# S7G7_footprint_simplified_w_ethernet_Pow.net
KiCad netlist of a schematic drawn in EAGLE
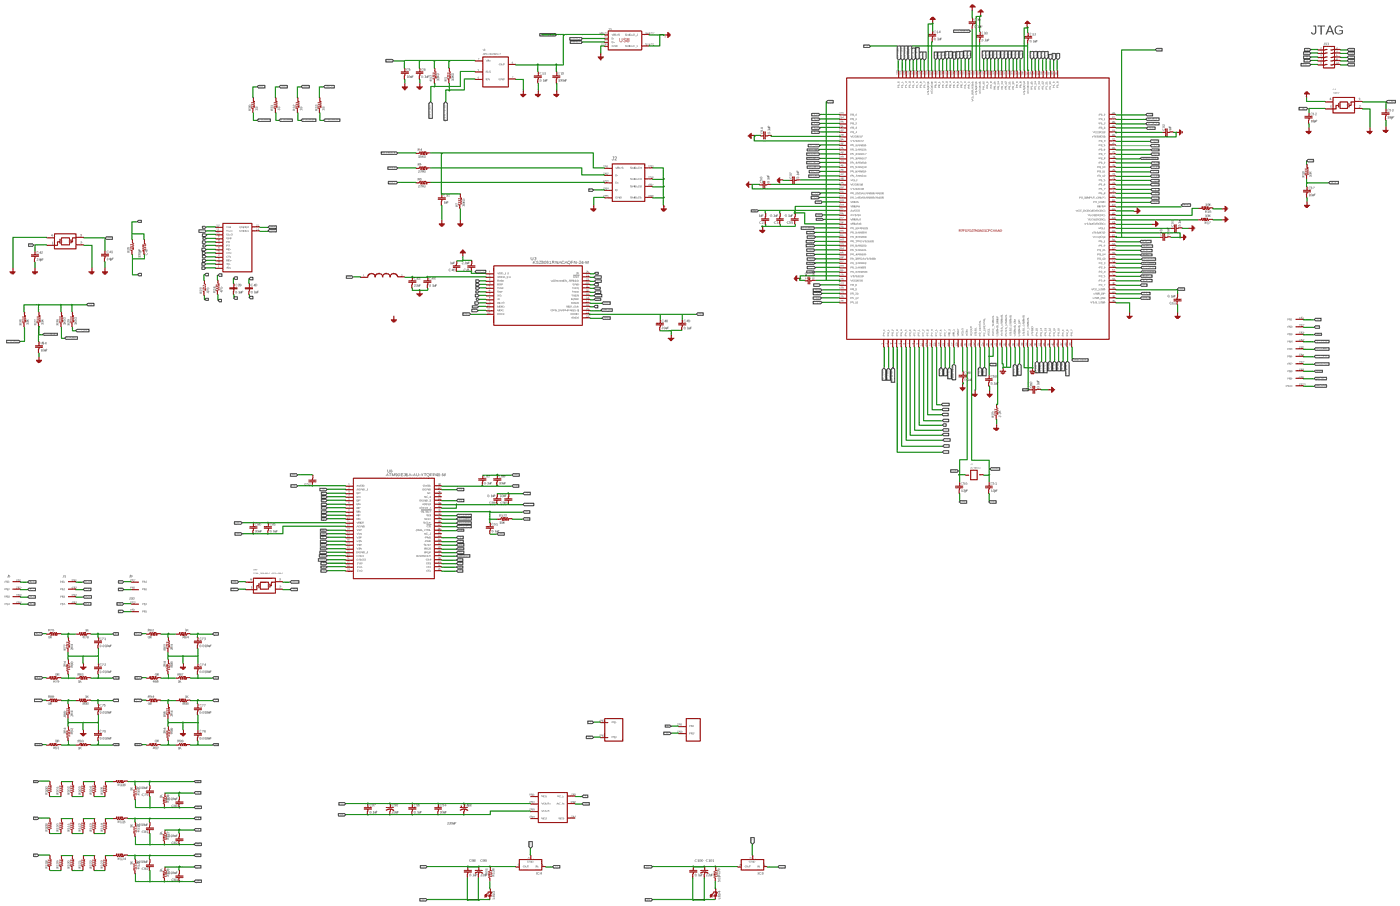
[diagram p0: schematic, sheet 1, overview]
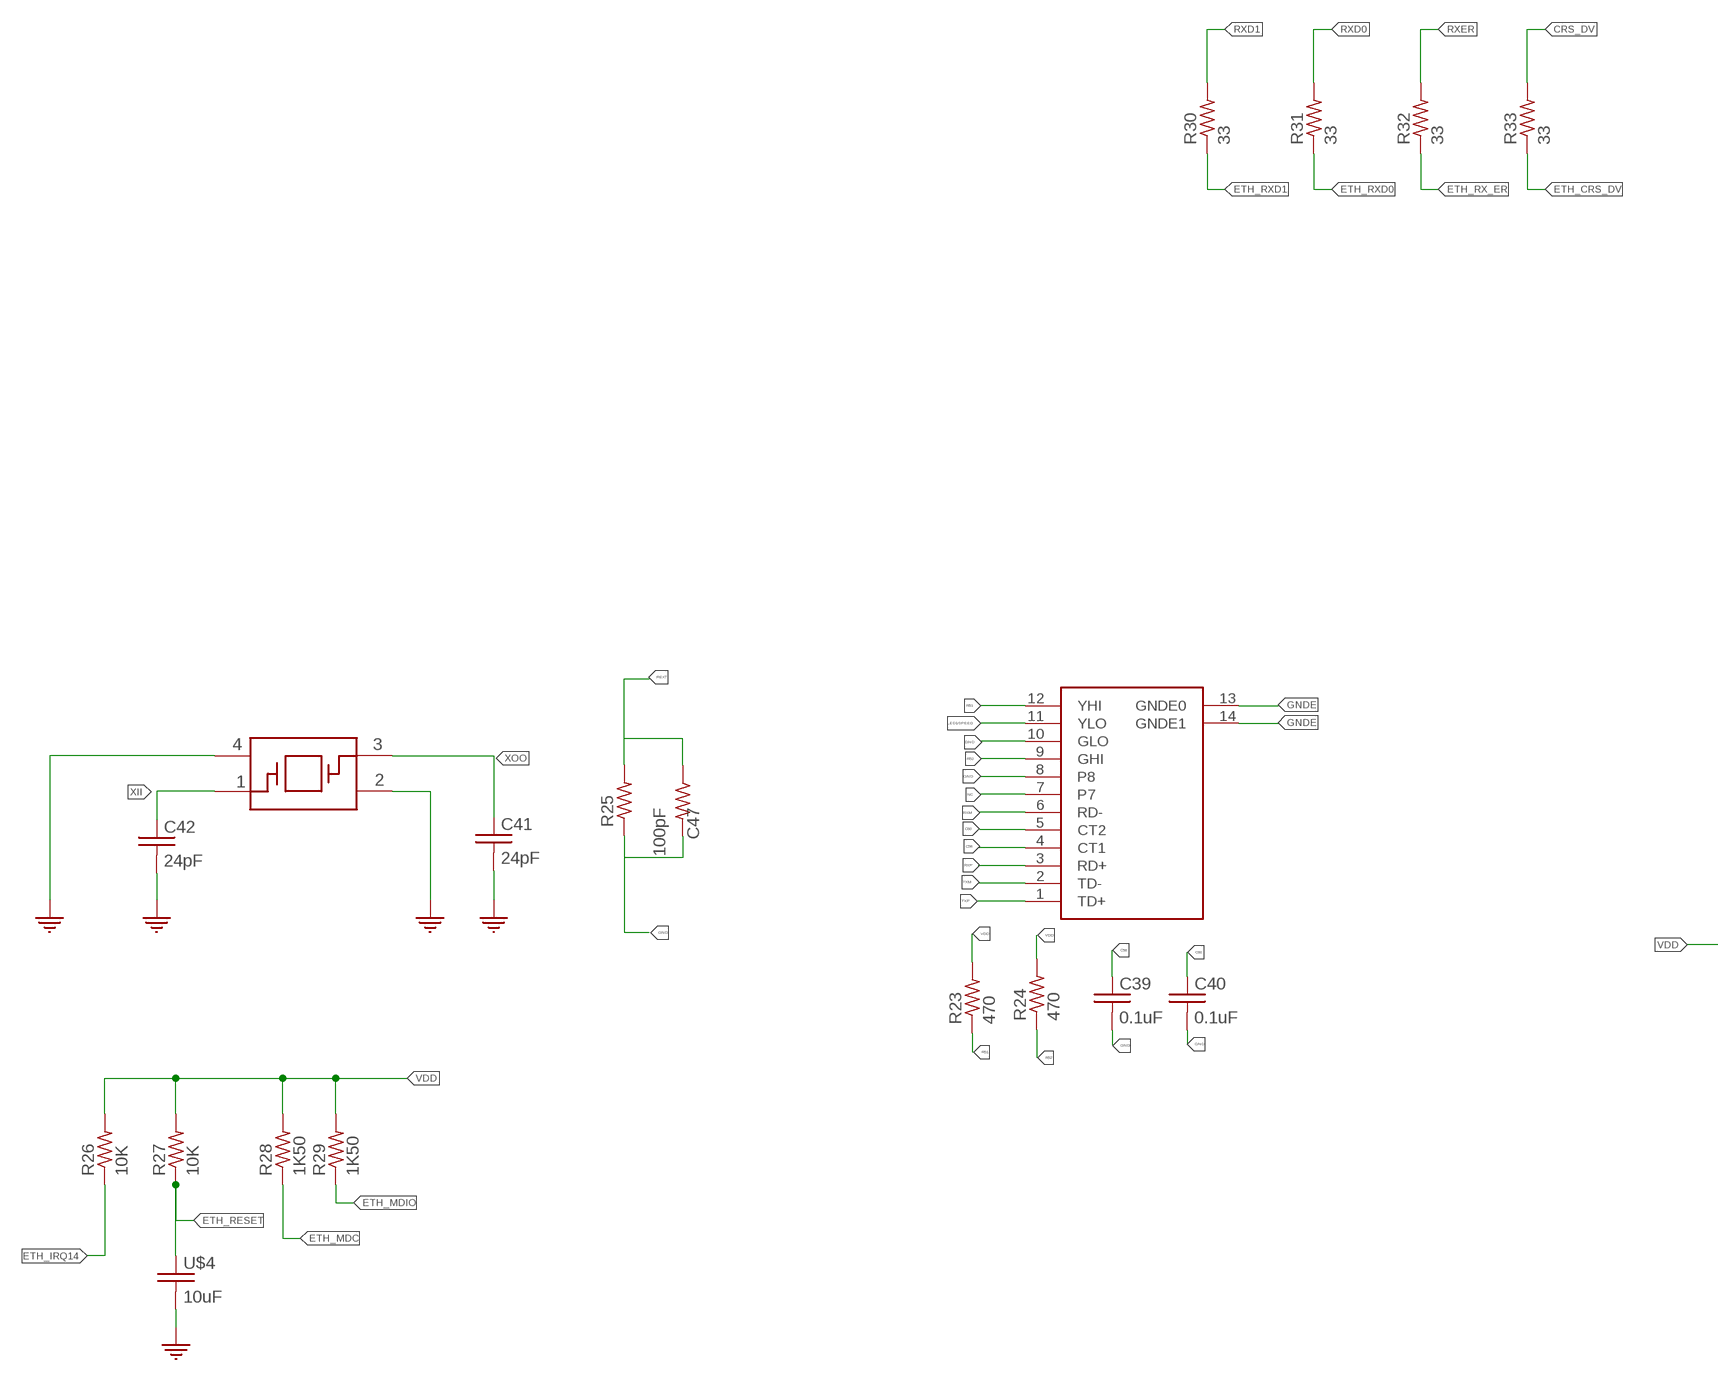
[diagram p1: schematic, sheet 1, part 1 of 6]
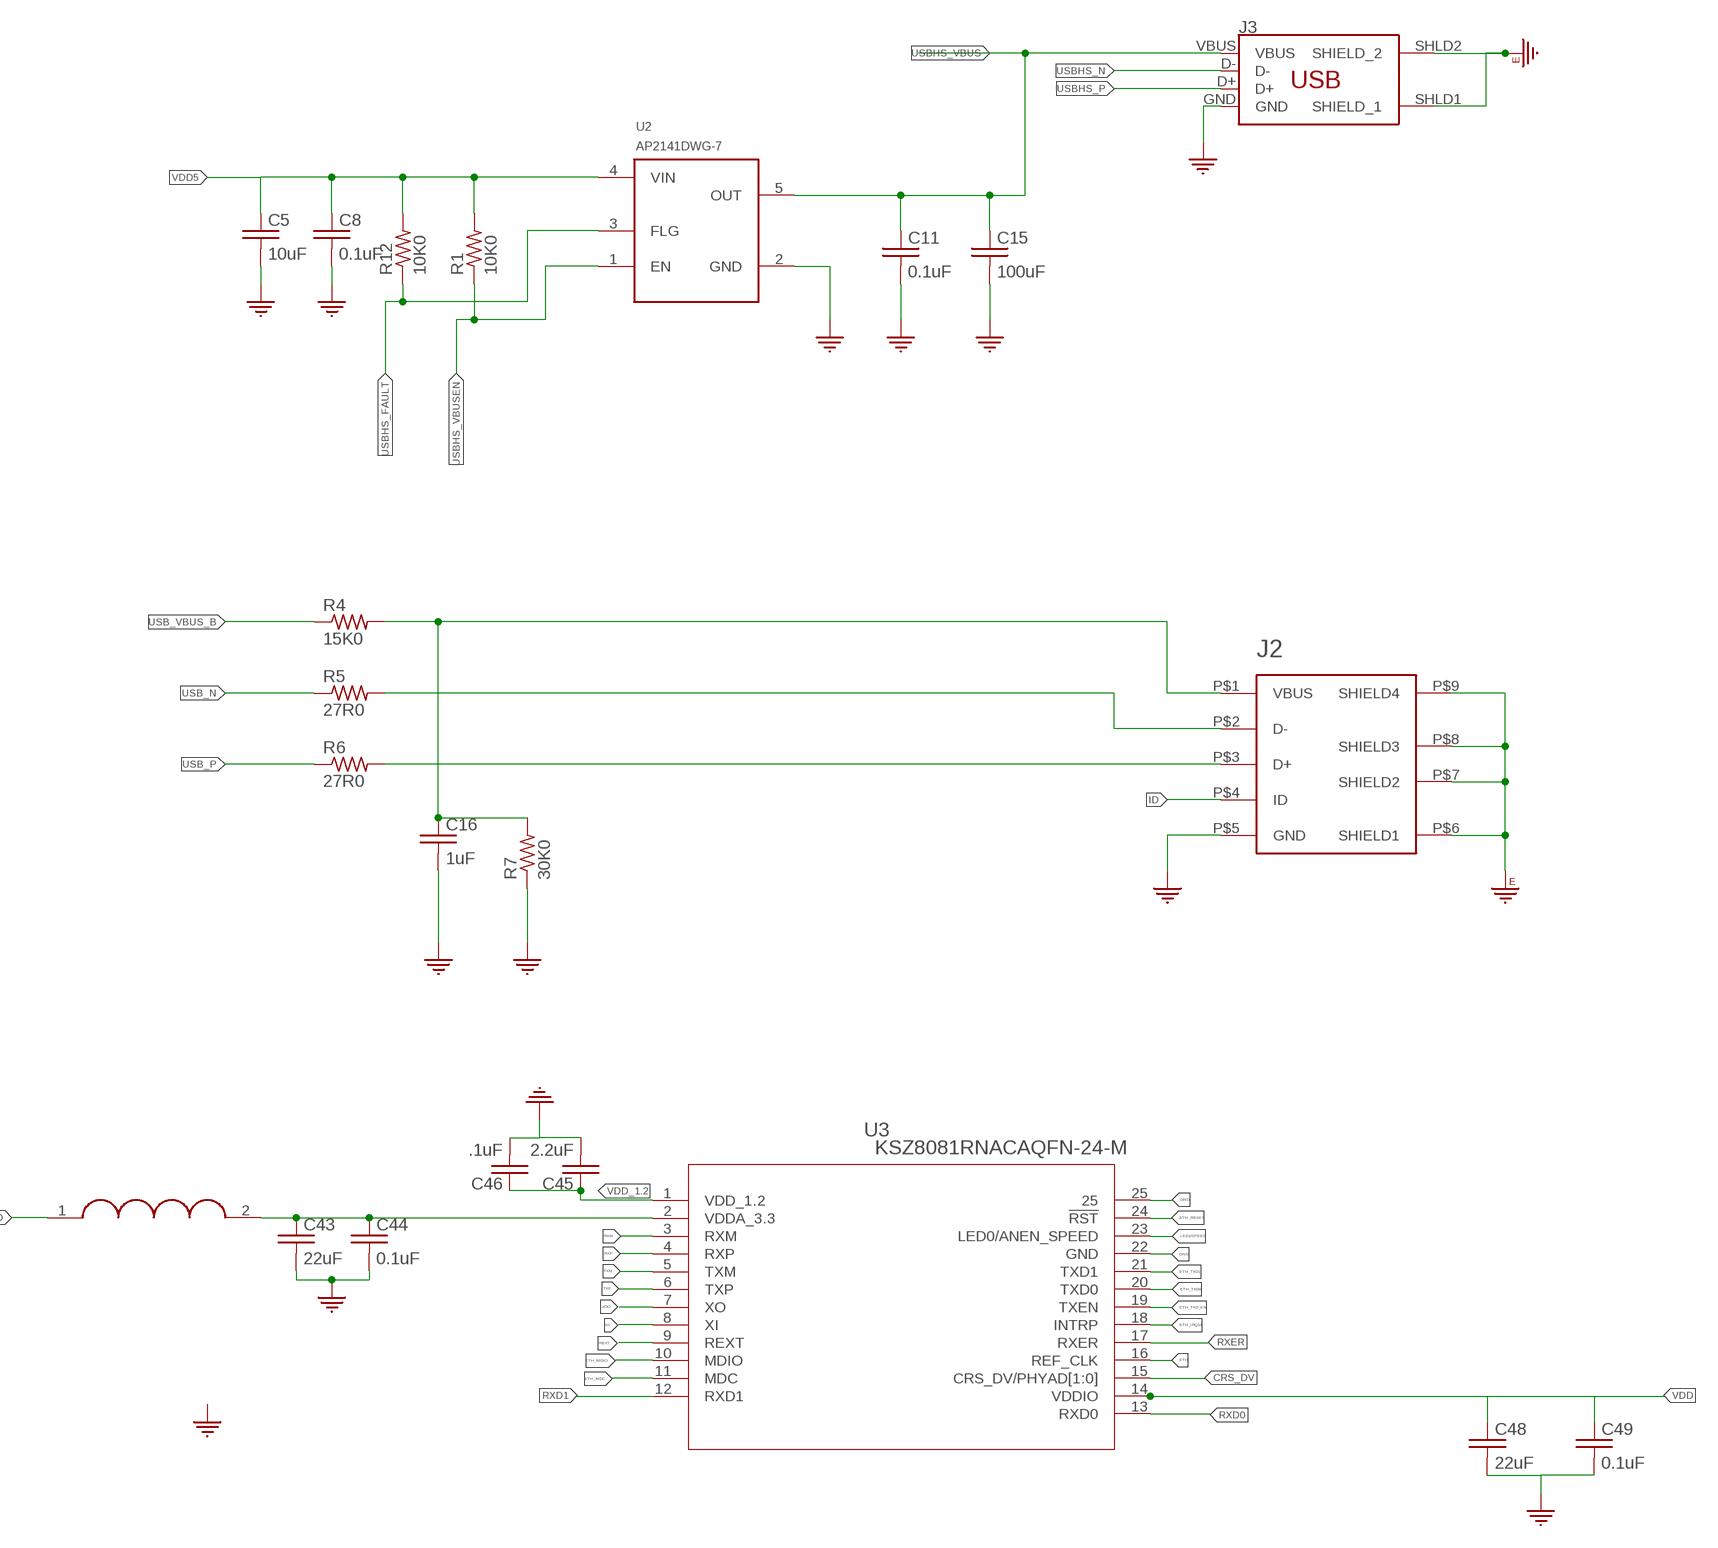
[diagram p2: schematic, sheet 1, part 2 of 6]
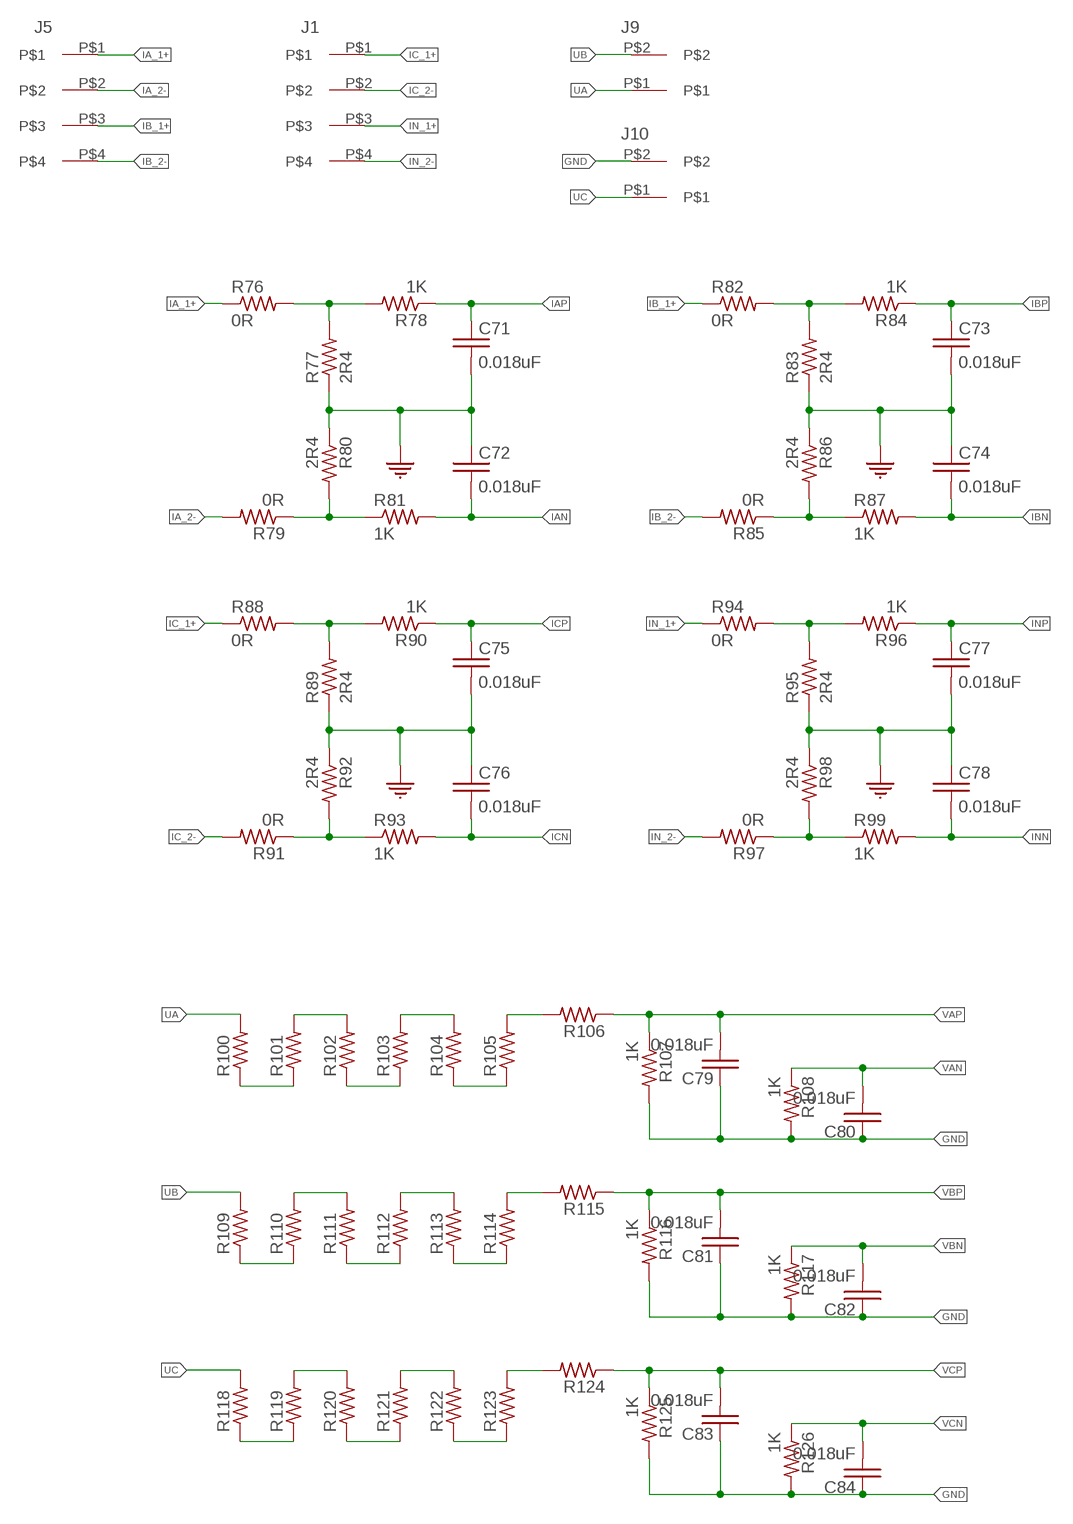
[diagram p3: schematic, sheet 1, part 3 of 6]
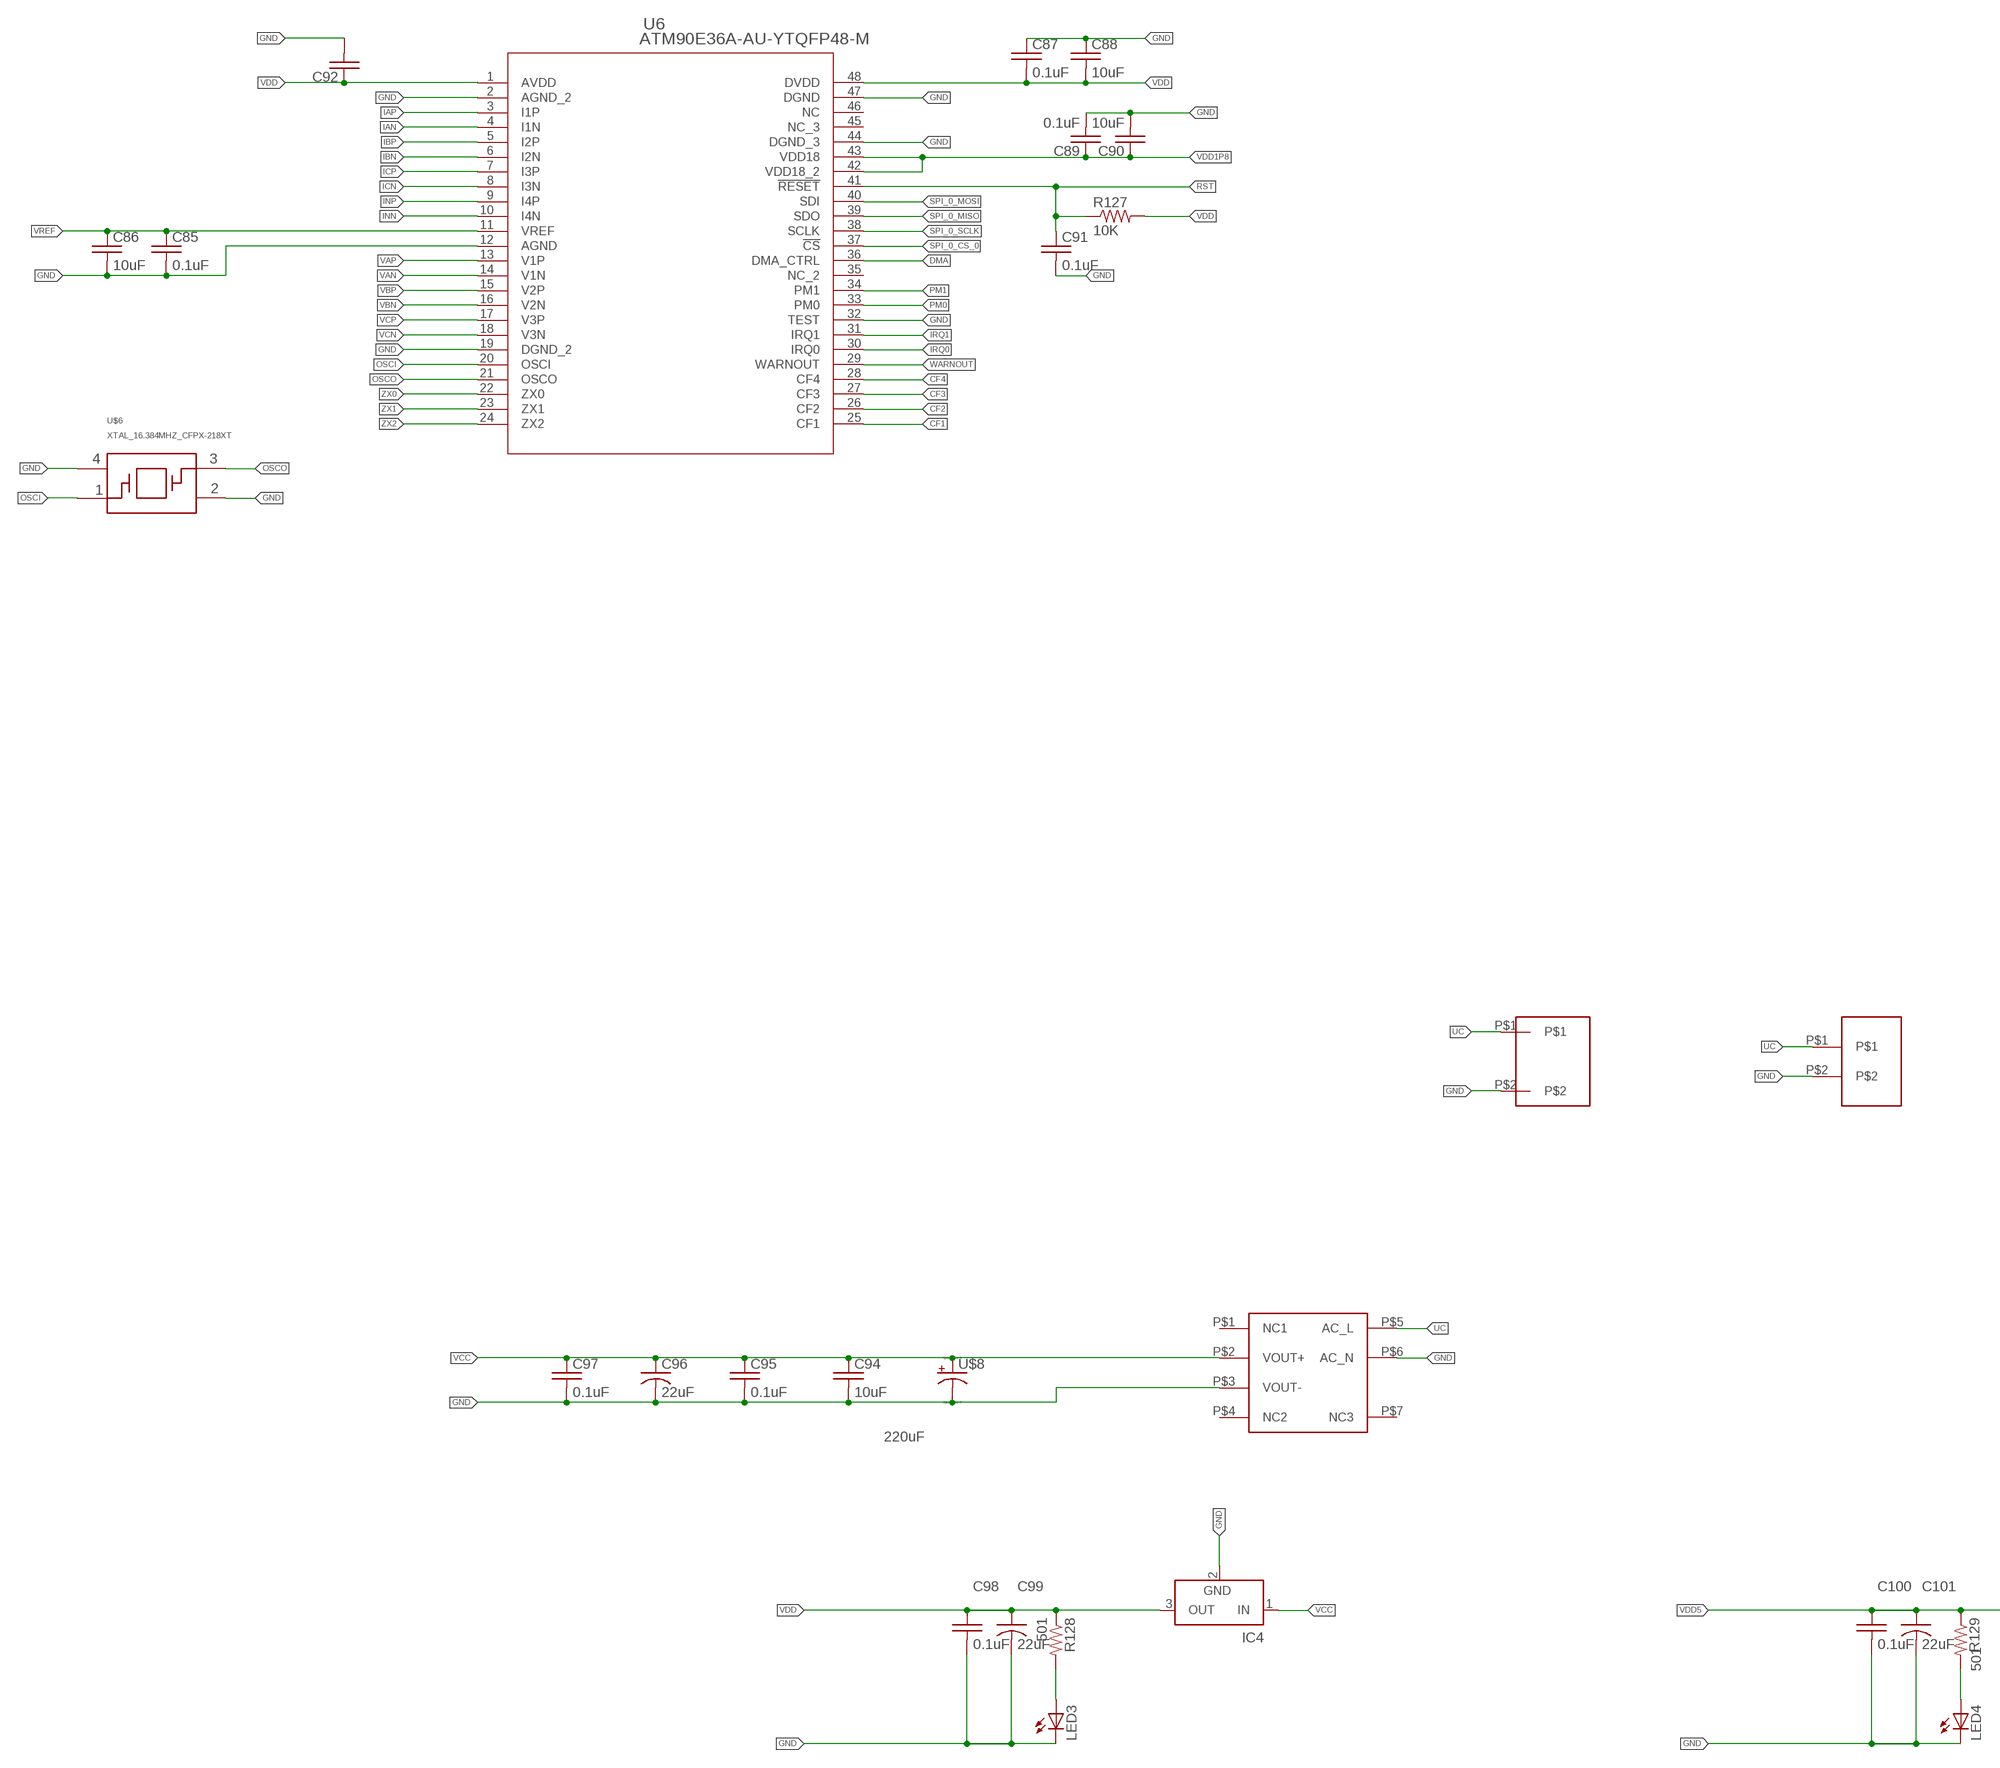
[diagram p4: schematic, sheet 1, part 4 of 6]
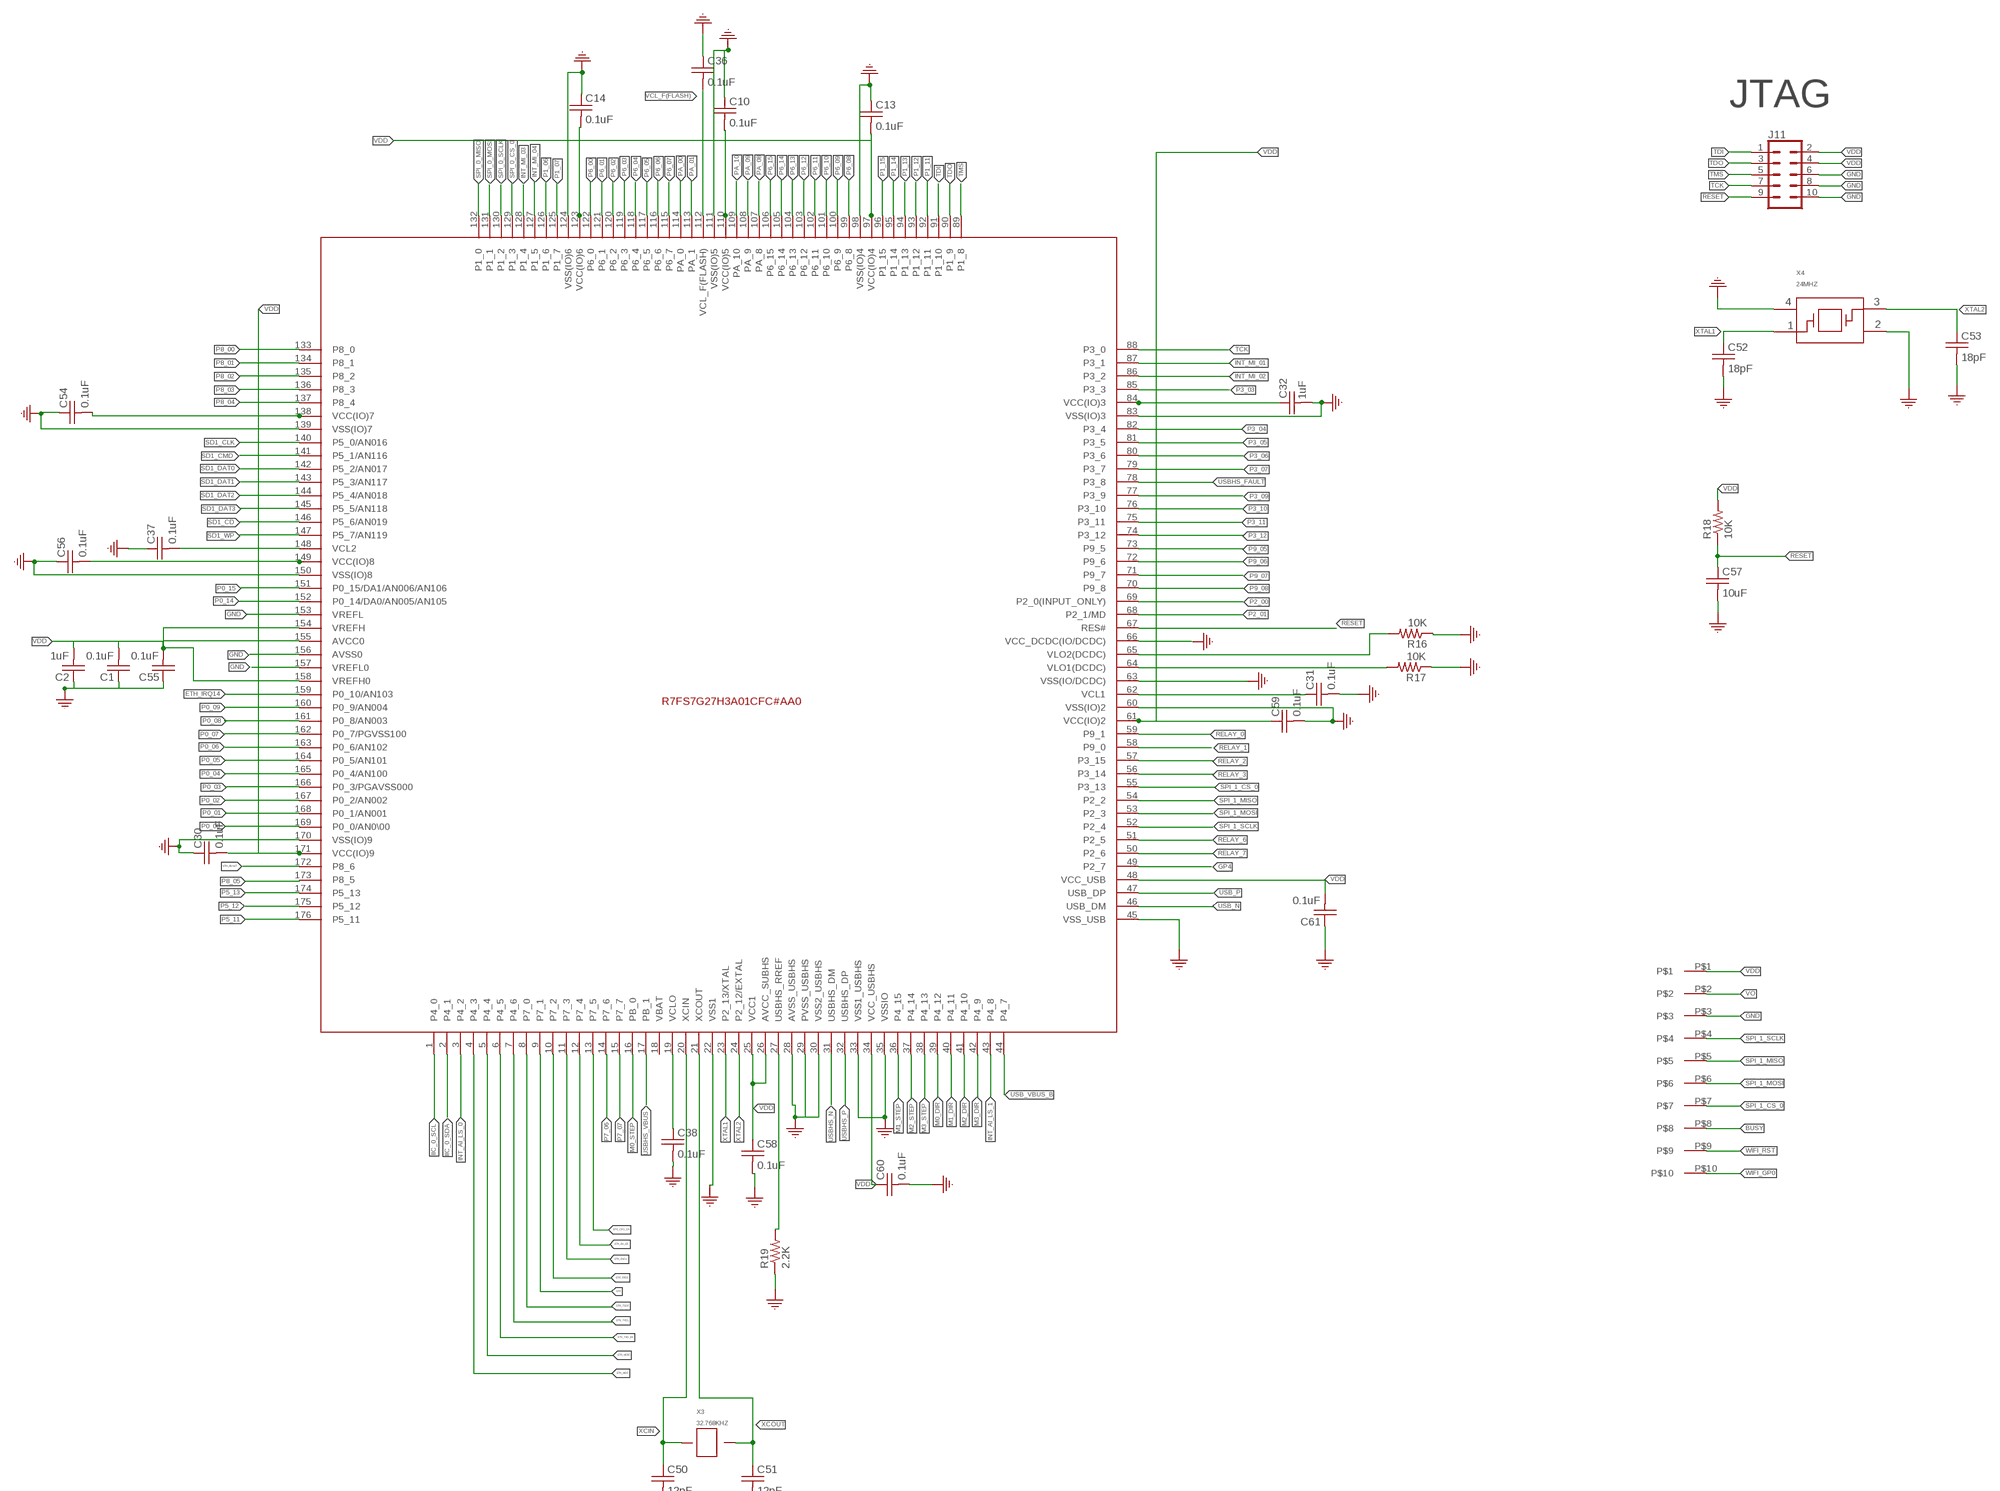
[diagram p5: schematic, sheet 1, part 5 of 6]
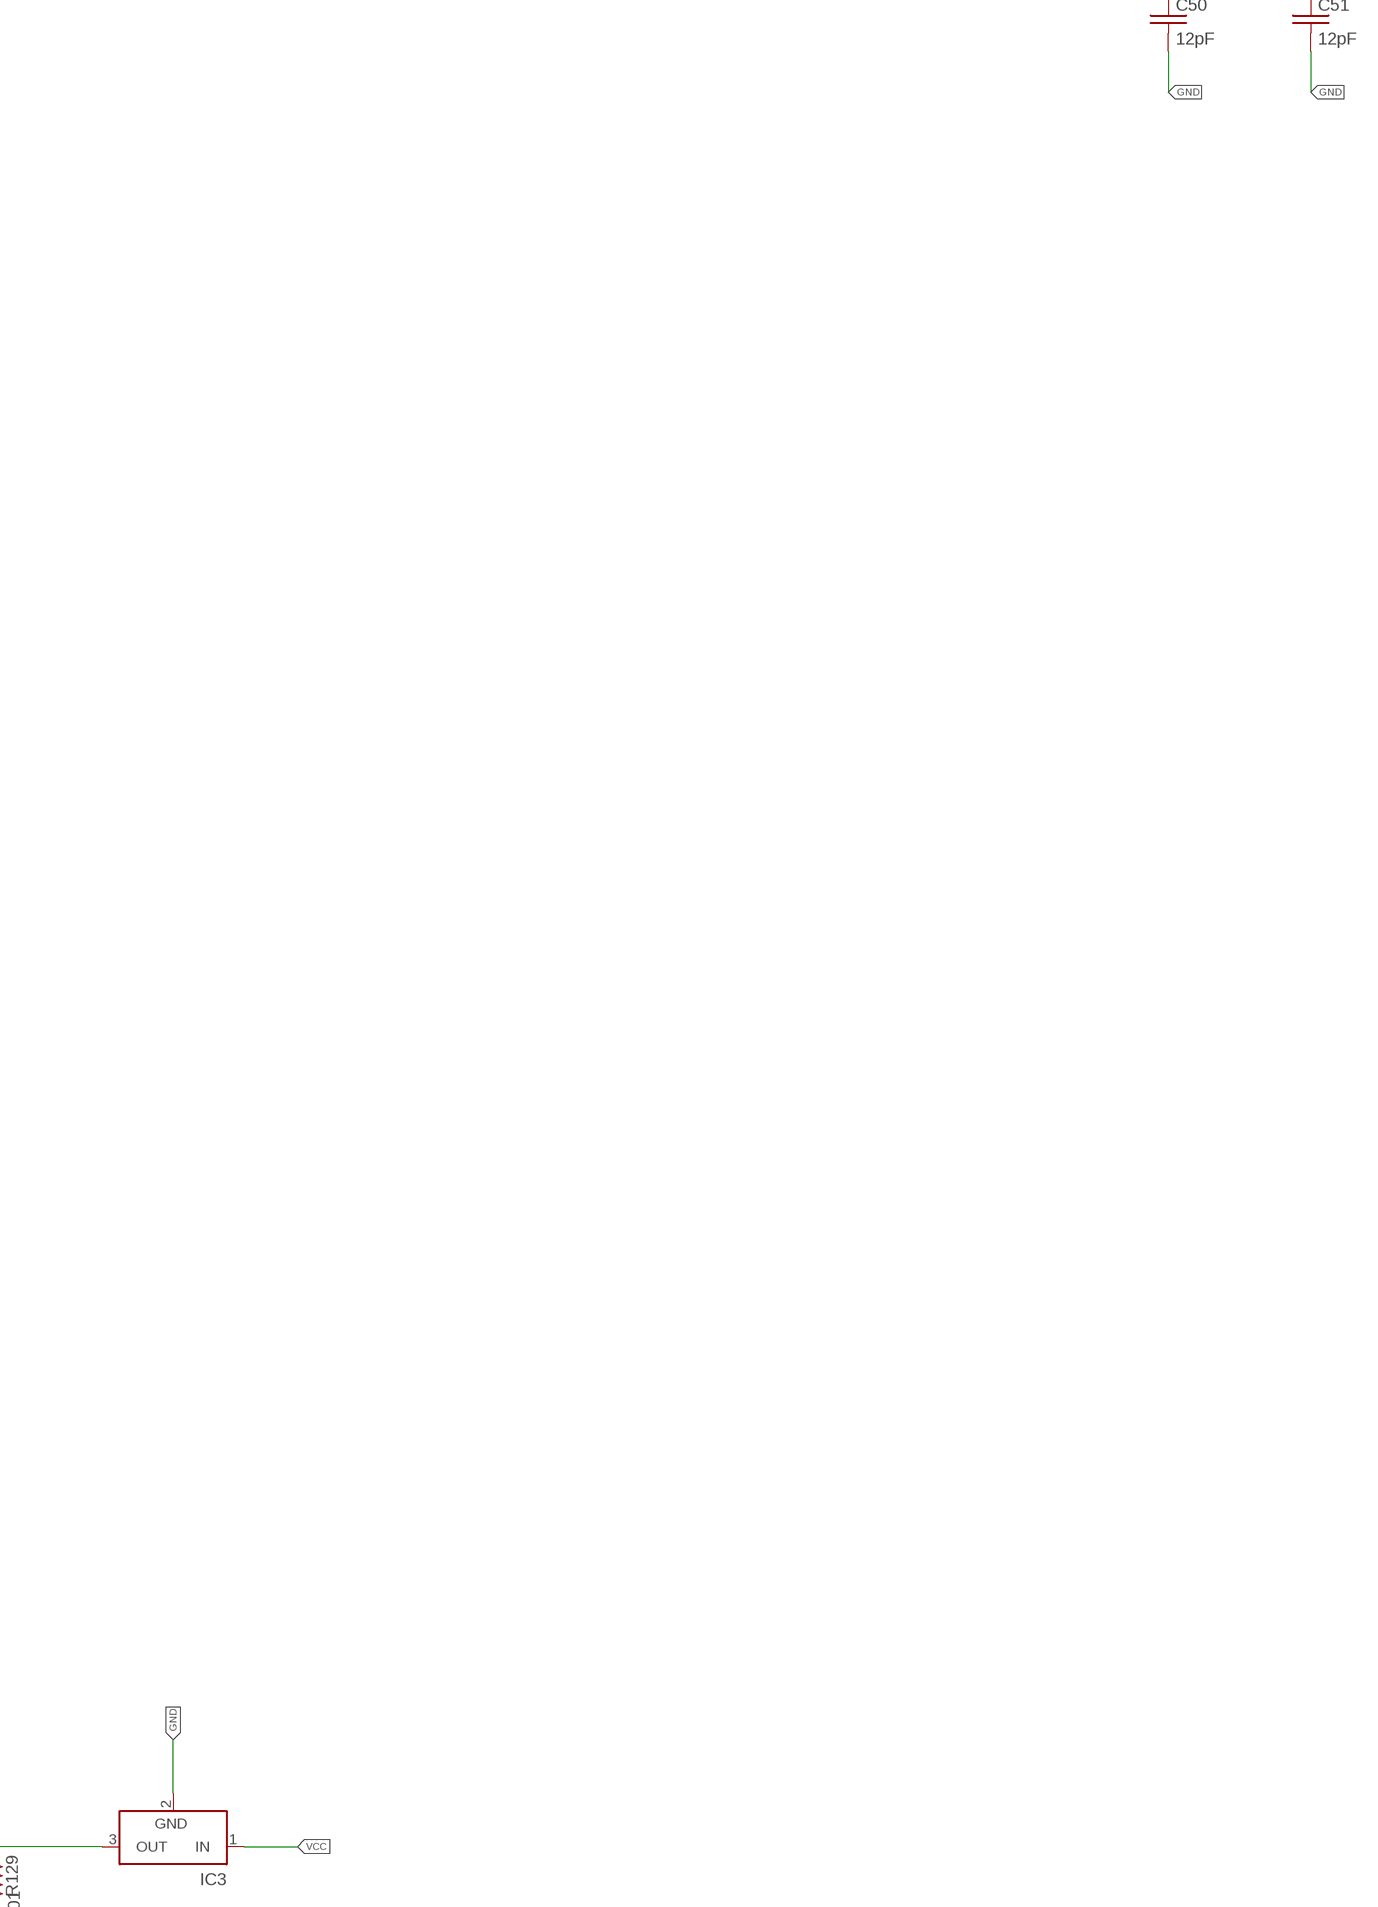
[diagram p6: schematic, sheet 1, part 6 of 6]

(export (version "E")
  (design (tool "Eeschema 10.0.6"))
  (components
    (comp (ref "C1")
      (value "0.1uF")
      (footprint "eagle-import:0402")
      (libsource (lib "eagle-import") (part "C_0402"))
    )
    (comp (ref "C2")
      (value "1uF")
      (footprint "eagle-import:0402")
      (libsource (lib "eagle-import") (part "C_0402"))
    )
    (comp (ref "C5")
      (value "10uF")
      (footprint "eagle-import:0402")
      (libsource (lib "eagle-import") (part "C_0402"))
    )
    (comp (ref "C8")
      (value "0.1uF")
      (footprint "eagle-import:0402")
      (libsource (lib "eagle-import") (part "C_0402"))
    )
    (comp (ref "C10")
      (value "0.1uF")
      (footprint "eagle-import:0402")
      (libsource (lib "eagle-import") (part "C_0402"))
    )
    (comp (ref "C11")
      (value "0.1uF")
      (footprint "eagle-import:0402")
      (libsource (lib "eagle-import") (part "C_0402"))
    )
    (comp (ref "C13")
      (value "0.1uF")
      (footprint "eagle-import:0402")
      (libsource (lib "eagle-import") (part "C_0402"))
    )
    (comp (ref "C14")
      (value "0.1uF")
      (footprint "eagle-import:0402")
      (libsource (lib "eagle-import") (part "C_0402"))
    )
    (comp (ref "C15")
      (value "100uF")
      (footprint "eagle-import:C1210")
      (libsource (lib "eagle-import") (part "C_1210"))
    )
    (comp (ref "C16")
      (value "1uF")
      (footprint "eagle-import:0402")
      (libsource (lib "eagle-import") (part "C_0402"))
    )
    (comp (ref "C30")
      (value "0.1uF")
      (footprint "eagle-import:0402")
      (libsource (lib "eagle-import") (part "C_0402"))
    )
    (comp (ref "C31")
      (value "0.1uF")
      (footprint "eagle-import:0402")
      (libsource (lib "eagle-import") (part "C_0402"))
    )
    (comp (ref "C32")
      (value "1uF")
      (footprint "eagle-import:0402")
      (libsource (lib "eagle-import") (part "C_0402"))
    )
    (comp (ref "C36")
      (value "0.1uF")
      (footprint "eagle-import:0402")
      (libsource (lib "eagle-import") (part "C_0402"))
    )
    (comp (ref "C37")
      (value "0.1uF")
      (footprint "eagle-import:0402")
      (libsource (lib "eagle-import") (part "C_0402"))
    )
    (comp (ref "C38")
      (value "0.1uF")
      (footprint "eagle-import:0402")
      (libsource (lib "eagle-import") (part "C_0402"))
    )
    (comp (ref "C39")
      (value "0.1uF")
      (footprint "eagle-import:0402")
      (libsource (lib "eagle-import") (part "C_0402"))
    )
    (comp (ref "C40")
      (value "0.1uF")
      (footprint "eagle-import:0402")
      (libsource (lib "eagle-import") (part "C_0402"))
    )
    (comp (ref "C41")
      (value "24pF")
      (footprint "eagle-import:0402")
      (libsource (lib "eagle-import") (part "C_0402"))
    )
    (comp (ref "C42")
      (value "24pF")
      (footprint "eagle-import:0402")
      (libsource (lib "eagle-import") (part "C_0402"))
    )
    (comp (ref "C43")
      (value "22uF")
      (footprint "eagle-import:0603")
      (libsource (lib "eagle-import") (part "C_0603"))
    )
    (comp (ref "C44")
      (value "0.1uF")
      (footprint "eagle-import:0402")
      (libsource (lib "eagle-import") (part "C_0402"))
    )
    (comp (ref "C45")
      (value "2.2uF")
      (footprint "eagle-import:0402")
      (libsource (lib "eagle-import") (part "C_0402"))
    )
    (comp (ref "C46")
      (value ".1uF")
      (footprint "eagle-import:0402")
      (libsource (lib "eagle-import") (part "C_0402"))
    )
    (comp (ref "C47")
      (value "100pF")
      (footprint "eagle-import:0402")
      (libsource (lib "eagle-import") (part "R_0402"))
    )
    (comp (ref "C48")
      (value "22uF")
      (footprint "eagle-import:0603")
      (libsource (lib "eagle-import") (part "C_0603"))
    )
    (comp (ref "C49")
      (value "0.1uF")
      (footprint "eagle-import:0402")
      (libsource (lib "eagle-import") (part "C_0402"))
    )
    (comp (ref "C50")
      (value "12pF")
      (footprint "eagle-import:0402")
      (libsource (lib "eagle-import") (part "C_0402"))
    )
    (comp (ref "C51")
      (value "12pF")
      (footprint "eagle-import:0402")
      (libsource (lib "eagle-import") (part "C_0402"))
    )
    (comp (ref "C52")
      (value "18pF")
      (footprint "eagle-import:0402")
      (libsource (lib "eagle-import") (part "C_0402"))
    )
    (comp (ref "C53")
      (value "18pF")
      (footprint "eagle-import:0402")
      (libsource (lib "eagle-import") (part "C_0402"))
    )
    (comp (ref "C54")
      (value "0.1uF")
      (footprint "eagle-import:0402")
      (libsource (lib "eagle-import") (part "C_0402"))
    )
    (comp (ref "C55")
      (value "0.1uF")
      (footprint "eagle-import:0402")
      (libsource (lib "eagle-import") (part "C_0402"))
    )
    (comp (ref "C56")
      (value "0.1uF")
      (footprint "eagle-import:0402")
      (libsource (lib "eagle-import") (part "C_0402"))
    )
    (comp (ref "C57")
      (value "10uF")
      (footprint "eagle-import:0402")
      (libsource (lib "eagle-import") (part "C_0402"))
    )
    (comp (ref "C58")
      (value "0.1uF")
      (footprint "eagle-import:0402")
      (libsource (lib "eagle-import") (part "C_0402"))
    )
    (comp (ref "C59")
      (value "0.1uF")
      (footprint "eagle-import:0402")
      (libsource (lib "eagle-import") (part "C_0402"))
    )
    (comp (ref "C60")
      (value "0.1uF")
      (footprint "eagle-import:0402")
      (libsource (lib "eagle-import") (part "C_0402"))
    )
    (comp (ref "C61")
      (value "0.1uF")
      (footprint "eagle-import:0402")
      (libsource (lib "eagle-import") (part "C_0402"))
    )
    (comp (ref "C71")
      (value "0.018uF")
      (footprint "eagle-import:0402")
      (libsource (lib "eagle-import") (part "C_0402"))
    )
    (comp (ref "C72")
      (value "0.018uF")
      (footprint "eagle-import:0402")
      (libsource (lib "eagle-import") (part "C_0402"))
    )
    (comp (ref "C73")
      (value "0.018uF")
      (footprint "eagle-import:0402")
      (libsource (lib "eagle-import") (part "C_0402"))
    )
    (comp (ref "C74")
      (value "0.018uF")
      (footprint "eagle-import:0402")
      (libsource (lib "eagle-import") (part "C_0402"))
    )
    (comp (ref "C75")
      (value "0.018uF")
      (footprint "eagle-import:0402")
      (libsource (lib "eagle-import") (part "C_0402"))
    )
    (comp (ref "C76")
      (value "0.018uF")
      (footprint "eagle-import:0402")
      (libsource (lib "eagle-import") (part "C_0402"))
    )
    (comp (ref "C77")
      (value "0.018uF")
      (footprint "eagle-import:0402")
      (libsource (lib "eagle-import") (part "C_0402"))
    )
    (comp (ref "C78")
      (value "0.018uF")
      (footprint "eagle-import:0402")
      (libsource (lib "eagle-import") (part "C_0402"))
    )
    (comp (ref "C79")
      (value "0.018uF")
      (footprint "eagle-import:0402")
      (libsource (lib "eagle-import") (part "C_0402"))
    )
    (comp (ref "C80")
      (value "0.018uF")
      (footprint "eagle-import:0402")
      (libsource (lib "eagle-import") (part "C_0402"))
    )
    (comp (ref "C81")
      (value "0.018uF")
      (footprint "eagle-import:0402")
      (libsource (lib "eagle-import") (part "C_0402"))
    )
    (comp (ref "C82")
      (value "0.018uF")
      (footprint "eagle-import:0402")
      (libsource (lib "eagle-import") (part "C_0402"))
    )
    (comp (ref "C83")
      (value "0.018uF")
      (footprint "eagle-import:0402")
      (libsource (lib "eagle-import") (part "C_0402"))
    )
    (comp (ref "C84")
      (value "0.018uF")
      (footprint "eagle-import:0402")
      (libsource (lib "eagle-import") (part "C_0402"))
    )
    (comp (ref "C85")
      (value "0.1uF")
      (footprint "eagle-import:0402")
      (libsource (lib "eagle-import") (part "C_0402"))
    )
    (comp (ref "C86")
      (value "10uF")
      (footprint "eagle-import:0402")
      (libsource (lib "eagle-import") (part "C_0402"))
    )
    (comp (ref "C87")
      (value "0.1uF")
      (footprint "eagle-import:0402")
      (libsource (lib "eagle-import") (part "C_0402"))
    )
    (comp (ref "C88")
      (value "10uF")
      (footprint "eagle-import:0402")
      (libsource (lib "eagle-import") (part "C_0402"))
    )
    (comp (ref "C89")
      (value "0.1uF")
      (footprint "eagle-import:0402")
      (libsource (lib "eagle-import") (part "C_0402"))
    )
    (comp (ref "C90")
      (value "10uF")
      (footprint "eagle-import:0402")
      (libsource (lib "eagle-import") (part "C_0402"))
    )
    (comp (ref "C91")
      (value "0.1uF")
      (footprint "eagle-import:0402")
      (libsource (lib "eagle-import") (part "C_0402"))
    )
    (comp (ref "C92")
      (value "C_0402")
      (footprint "eagle-import:0402")
      (libsource (lib "eagle-import") (part "C_0402"))
    )
    (comp (ref "C93")
      (value "CAP_THIN_FILM_TDK_32922CAP")
      (footprint "eagle-import:CAP_THIN_FILM_32922")
      (libsource (lib "eagle-import") (part "CAP_THIN_FILM_TDK_32922CAP"))
    )
    (comp (ref "C94")
      (value "10uF")
      (footprint "eagle-import:0402")
      (libsource (lib "eagle-import") (part "C_0402"))
    )
    (comp (ref "C95")
      (value "0.1uF")
      (footprint "eagle-import:0402")
      (libsource (lib "eagle-import") (part "C_0402"))
    )
    (comp (ref "C96")
      (value "22uF")
      (footprint "eagle-import:C1206")
      (libsource (lib "eagle-import") (part "C-USC1206"))
    )
    (comp (ref "C97")
      (value "0.1uF")
      (footprint "eagle-import:0402")
      (libsource (lib "eagle-import") (part "C_0402"))
    )
    (comp (ref "C98")
      (value "0.1uF")
      (footprint "eagle-import:0402")
      (libsource (lib "eagle-import") (part "C_0402"))
    )
    (comp (ref "C99")
      (value "22uF")
      (footprint "eagle-import:C1206")
      (libsource (lib "eagle-import") (part "C-USC1206"))
    )
    (comp (ref "C100")
      (value "0.1uF")
      (footprint "eagle-import:0402")
      (libsource (lib "eagle-import") (part "C_0402"))
    )
    (comp (ref "C101")
      (value "22uF")
      (footprint "eagle-import:C1206")
      (libsource (lib "eagle-import") (part "C-USC1206"))
    )
    (comp (ref "FB2/2")
      (value "FB_0805_120_OHM")
      (footprint "eagle-import:0805")
      (libsource (lib "eagle-import") (part "FB_0805_120_OHM"))
    )
    (comp (ref "IC3")
      (value "LT1129CST5")
      (footprint "eagle-import:SOT223")
      (fields (field (name "MPN") "LT1129CST-5#PBF"))
      (libsource (lib "eagle-import") (part "LT1129CST5"))
    )
    (comp (ref "IC4")
      (value "LT1129CST3")
      (footprint "eagle-import:SOT223")
      (fields (field (name "MPN") "LT1129CST-5#PBF"))
      (libsource (lib "eagle-import") (part "LT1129CST3"))
    )
    (comp (ref "J1")
      (value "3.81MM_1_X_4_RT_ANGLE_PLUG_HEADER")
      (footprint "eagle-import:1X4_3.81MM_PITCH")
      (libsource (lib "eagle-import") (part "3.81MM_1_X_4_RT_ANGLE_PLUG_HEADER"))
    )
    (comp (ref "J2")
      (value "USB_MICRO-B")
      (footprint "eagle-import:USB_MICRO-B")
      (libsource (lib "eagle-import") (part "USB_MICRO-B"))
    )
    (comp (ref "J3")
      (value "USB_A")
      (footprint "eagle-import:USB_A_SMT")
      (libsource (lib "eagle-import") (part "USB_A"))
    )
    (comp (ref "J4")
      (value "RJ45_WITH_ELEC")
      (footprint "eagle-import:RJ45_TH_ELEC")
      (libsource (lib "eagle-import") (part "RJ45_WITH_ELEC"))
    )
    (comp (ref "J5")
      (value "3.81MM_1_X_4_RT_ANGLE_PLUG_HEADER")
      (footprint "eagle-import:1X4_3.81MM_PITCH")
      (libsource (lib "eagle-import") (part "3.81MM_1_X_4_RT_ANGLE_PLUG_HEADER"))
    )
    (comp (ref "J9")
      (value "3.81MM_1_X_2_RT_ANGLE_PLUG_HEADER")
      (footprint "eagle-import:2_3.81MM_PITCH")
      (libsource (lib "eagle-import") (part "3.81MM_1_X_2_RT_ANGLE_PLUG_HEADER"))
    )
    (comp (ref "J10")
      (value "3.81MM_1_X_2_RT_ANGLE_PLUG_HEADER")
      (footprint "eagle-import:2_3.81MM_PITCH")
      (libsource (lib "eagle-import") (part "3.81MM_1_X_2_RT_ANGLE_PLUG_HEADER"))
    )
    (comp (ref "J11")
      (value "CONN_05X2PTH")
      (footprint "eagle-import:2X5")
      (libsource (lib "eagle-import") (part "CONN_05X2PTH"))
    )
    (comp (ref "LED3")
      (value "LED_0805_GREEN")
      (footprint "eagle-import:LED_0805_GREEN")
      (libsource (lib "eagle-import") (part "LED_0805_GREEN"))
    )
    (comp (ref "LED4")
      (value "LED_0805_GREEN")
      (footprint "eagle-import:LED_0805_GREEN")
      (libsource (lib "eagle-import") (part "LED_0805_GREEN"))
    )
    (comp (ref "R1")
      (value "10K0")
      (footprint "eagle-import:0402")
      (libsource (lib "eagle-import") (part "R_0402"))
    )
    (comp (ref "R4")
      (value "15K0")
      (footprint "eagle-import:0402")
      (libsource (lib "eagle-import") (part "R_0402"))
    )
    (comp (ref "R5")
      (value "27R0")
      (footprint "eagle-import:0402")
      (libsource (lib "eagle-import") (part "R_0402"))
    )
    (comp (ref "R6")
      (value "27R0")
      (footprint "eagle-import:0402")
      (libsource (lib "eagle-import") (part "R_0402"))
    )
    (comp (ref "R7")
      (value "30K0")
      (footprint "eagle-import:0402")
      (libsource (lib "eagle-import") (part "R_0402"))
    )
    (comp (ref "R12")
      (value "10K0")
      (footprint "eagle-import:0402")
      (libsource (lib "eagle-import") (part "R_0402"))
    )
    (comp (ref "R16")
      (value "10K")
      (footprint "eagle-import:0402")
      (libsource (lib "eagle-import") (part "R_0402"))
    )
    (comp (ref "R17")
      (value "10K")
      (footprint "eagle-import:0402")
      (libsource (lib "eagle-import") (part "R_0402"))
    )
    (comp (ref "R18")
      (value "10K")
      (footprint "eagle-import:0402")
      (libsource (lib "eagle-import") (part "R_0402"))
    )
    (comp (ref "R19")
      (value "2.2K")
      (footprint "eagle-import:0402")
      (libsource (lib "eagle-import") (part "R_0402"))
    )
    (comp (ref "R23")
      (value "470")
      (footprint "eagle-import:0402")
      (libsource (lib "eagle-import") (part "R_0402"))
    )
    (comp (ref "R24")
      (value "470")
      (footprint "eagle-import:0402")
      (libsource (lib "eagle-import") (part "R_0402"))
    )
    (comp (ref "R25")
      (value "6k49")
      (footprint "eagle-import:0402")
      (libsource (lib "eagle-import") (part "R_0402"))
    )
    (comp (ref "R26")
      (value "10K")
      (footprint "eagle-import:0402")
      (libsource (lib "eagle-import") (part "R_0402"))
    )
    (comp (ref "R27")
      (value "10K")
      (footprint "eagle-import:0402")
      (libsource (lib "eagle-import") (part "R_0402"))
    )
    (comp (ref "R28")
      (value "1K50")
      (footprint "eagle-import:0402")
      (libsource (lib "eagle-import") (part "R_0402"))
    )
    (comp (ref "R29")
      (value "1K50")
      (footprint "eagle-import:0402")
      (libsource (lib "eagle-import") (part "R_0402"))
    )
    (comp (ref "R30")
      (value "33")
      (footprint "eagle-import:0402")
      (libsource (lib "eagle-import") (part "R_0402"))
    )
    (comp (ref "R31")
      (value "33")
      (footprint "eagle-import:0402")
      (libsource (lib "eagle-import") (part "R_0402"))
    )
    (comp (ref "R32")
      (value "33")
      (footprint "eagle-import:0402")
      (libsource (lib "eagle-import") (part "R_0402"))
    )
    (comp (ref "R33")
      (value "33")
      (footprint "eagle-import:0402")
      (libsource (lib "eagle-import") (part "R_0402"))
    )
    (comp (ref "R76")
      (value "0R")
      (footprint "eagle-import:0402")
      (libsource (lib "eagle-import") (part "R_0402"))
    )
    (comp (ref "R77")
      (value "2R4")
      (footprint "eagle-import:0402")
      (libsource (lib "eagle-import") (part "R_0402"))
    )
    (comp (ref "R78")
      (value "1K")
      (footprint "eagle-import:0402")
      (libsource (lib "eagle-import") (part "R_0402"))
    )
    (comp (ref "R79")
      (value "0R")
      (footprint "eagle-import:0402")
      (libsource (lib "eagle-import") (part "R_0402"))
    )
    (comp (ref "R80")
      (value "2R4")
      (footprint "eagle-import:0402")
      (libsource (lib "eagle-import") (part "R_0402"))
    )
    (comp (ref "R81")
      (value "1K")
      (footprint "eagle-import:0402")
      (libsource (lib "eagle-import") (part "R_0402"))
    )
    (comp (ref "R82")
      (value "0R")
      (footprint "eagle-import:0402")
      (libsource (lib "eagle-import") (part "R_0402"))
    )
    (comp (ref "R83")
      (value "2R4")
      (footprint "eagle-import:0402")
      (libsource (lib "eagle-import") (part "R_0402"))
    )
    (comp (ref "R84")
      (value "1K")
      (footprint "eagle-import:0402")
      (libsource (lib "eagle-import") (part "R_0402"))
    )
    (comp (ref "R85")
      (value "0R")
      (footprint "eagle-import:0402")
      (libsource (lib "eagle-import") (part "R_0402"))
    )
    (comp (ref "R86")
      (value "2R4")
      (footprint "eagle-import:0402")
      (libsource (lib "eagle-import") (part "R_0402"))
    )
    (comp (ref "R87")
      (value "1K")
      (footprint "eagle-import:0402")
      (libsource (lib "eagle-import") (part "R_0402"))
    )
    (comp (ref "R88")
      (value "0R")
      (footprint "eagle-import:0402")
      (libsource (lib "eagle-import") (part "R_0402"))
    )
    (comp (ref "R89")
      (value "2R4")
      (footprint "eagle-import:0402")
      (libsource (lib "eagle-import") (part "R_0402"))
    )
    (comp (ref "R90")
      (value "1K")
      (footprint "eagle-import:0402")
      (libsource (lib "eagle-import") (part "R_0402"))
    )
    (comp (ref "R91")
      (value "0R")
      (footprint "eagle-import:0402")
      (libsource (lib "eagle-import") (part "R_0402"))
    )
    (comp (ref "R92")
      (value "2R4")
      (footprint "eagle-import:0402")
      (libsource (lib "eagle-import") (part "R_0402"))
    )
    (comp (ref "R93")
      (value "1K")
      (footprint "eagle-import:0402")
      (libsource (lib "eagle-import") (part "R_0402"))
    )
    (comp (ref "R94")
      (value "0R")
      (footprint "eagle-import:0402")
      (libsource (lib "eagle-import") (part "R_0402"))
    )
    (comp (ref "R95")
      (value "2R4")
      (footprint "eagle-import:0402")
      (libsource (lib "eagle-import") (part "R_0402"))
    )
    (comp (ref "R96")
      (value "1K")
      (footprint "eagle-import:0402")
      (libsource (lib "eagle-import") (part "R_0402"))
    )
    (comp (ref "R97")
      (value "0R")
      (footprint "eagle-import:0402")
      (libsource (lib "eagle-import") (part "R_0402"))
    )
    (comp (ref "R98")
      (value "2R4")
      (footprint "eagle-import:0402")
      (libsource (lib "eagle-import") (part "R_0402"))
    )
    (comp (ref "R99")
      (value "1K")
      (footprint "eagle-import:0402")
      (libsource (lib "eagle-import") (part "R_0402"))
    )
    (comp (ref "R100")
      (value "R_0402")
      (footprint "eagle-import:0402")
      (libsource (lib "eagle-import") (part "R_0402"))
    )
    (comp (ref "R101")
      (value "R_0402")
      (footprint "eagle-import:0402")
      (libsource (lib "eagle-import") (part "R_0402"))
    )
    (comp (ref "R102")
      (value "R_0402")
      (footprint "eagle-import:0402")
      (libsource (lib "eagle-import") (part "R_0402"))
    )
    (comp (ref "R103")
      (value "R_0402")
      (footprint "eagle-import:0402")
      (libsource (lib "eagle-import") (part "R_0402"))
    )
    (comp (ref "R104")
      (value "R_0402")
      (footprint "eagle-import:0402")
      (libsource (lib "eagle-import") (part "R_0402"))
    )
    (comp (ref "R105")
      (value "R_0402")
      (footprint "eagle-import:0402")
      (libsource (lib "eagle-import") (part "R_0402"))
    )
    (comp (ref "R106")
      (value "R_0402")
      (footprint "eagle-import:0402")
      (libsource (lib "eagle-import") (part "R_0402"))
    )
    (comp (ref "R107")
      (value "1K")
      (footprint "eagle-import:0402")
      (libsource (lib "eagle-import") (part "R_0402"))
    )
    (comp (ref "R108")
      (value "1K")
      (footprint "eagle-import:0402")
      (libsource (lib "eagle-import") (part "R_0402"))
    )
    (comp (ref "R109")
      (value "R_0402")
      (footprint "eagle-import:0402")
      (libsource (lib "eagle-import") (part "R_0402"))
    )
    (comp (ref "R110")
      (value "R_0402")
      (footprint "eagle-import:0402")
      (libsource (lib "eagle-import") (part "R_0402"))
    )
    (comp (ref "R111")
      (value "R_0402")
      (footprint "eagle-import:0402")
      (libsource (lib "eagle-import") (part "R_0402"))
    )
    (comp (ref "R112")
      (value "R_0402")
      (footprint "eagle-import:0402")
      (libsource (lib "eagle-import") (part "R_0402"))
    )
    (comp (ref "R113")
      (value "R_0402")
      (footprint "eagle-import:0402")
      (libsource (lib "eagle-import") (part "R_0402"))
    )
    (comp (ref "R114")
      (value "R_0402")
      (footprint "eagle-import:0402")
      (libsource (lib "eagle-import") (part "R_0402"))
    )
    (comp (ref "R115")
      (value "R_0402")
      (footprint "eagle-import:0402")
      (libsource (lib "eagle-import") (part "R_0402"))
    )
    (comp (ref "R116")
      (value "1K")
      (footprint "eagle-import:0402")
      (libsource (lib "eagle-import") (part "R_0402"))
    )
    (comp (ref "R117")
      (value "1K")
      (footprint "eagle-import:0402")
      (libsource (lib "eagle-import") (part "R_0402"))
    )
    (comp (ref "R118")
      (value "R_0402")
      (footprint "eagle-import:0402")
      (libsource (lib "eagle-import") (part "R_0402"))
    )
    (comp (ref "R119")
      (value "R_0402")
      (footprint "eagle-import:0402")
      (libsource (lib "eagle-import") (part "R_0402"))
    )
    (comp (ref "R120")
      (value "R_0402")
      (footprint "eagle-import:0402")
      (libsource (lib "eagle-import") (part "R_0402"))
    )
    (comp (ref "R121")
      (value "R_0402")
      (footprint "eagle-import:0402")
      (libsource (lib "eagle-import") (part "R_0402"))
    )
    (comp (ref "R122")
      (value "R_0402")
      (footprint "eagle-import:0402")
      (libsource (lib "eagle-import") (part "R_0402"))
    )
    (comp (ref "R123")
      (value "R_0402")
      (footprint "eagle-import:0402")
      (libsource (lib "eagle-import") (part "R_0402"))
    )
    (comp (ref "R124")
      (value "R_0402")
      (footprint "eagle-import:0402")
      (libsource (lib "eagle-import") (part "R_0402"))
    )
    (comp (ref "R125")
      (value "1K")
      (footprint "eagle-import:0402")
      (libsource (lib "eagle-import") (part "R_0402"))
    )
    (comp (ref "R126")
      (value "1K")
      (footprint "eagle-import:0402")
      (libsource (lib "eagle-import") (part "R_0402"))
    )
    (comp (ref "R127")
      (value "10K")
      (footprint "eagle-import:0402")
      (libsource (lib "eagle-import") (part "R_0402"))
    )
    (comp (ref "R128")
      (value "501")
      (footprint "eagle-import:0402")
      (libsource (lib "eagle-import") (part "R_0402"))
    )
    (comp (ref "R129")
      (value "501")
      (footprint "eagle-import:0402")
      (libsource (lib "eagle-import") (part "R_0402"))
    )
    (comp (ref "U$1")
      (value "1_X_10_HEADER_GENERIC_.1INCH")
      (footprint "eagle-import:HEADER_1_X_10_.1_INCH")
      (libsource (lib "eagle-import") (part "1_X_10_HEADER_GENERIC_.1INCH"))
    )
    (comp (ref "U$3")
      (value "XTAL_25_MHZ")
      (footprint "eagle-import:SMD_3225")
      (libsource (lib "eagle-import") (part "XTAL_25_MHZ"))
    )
    (comp (ref "U$4")
      (value "10uF")
      (footprint "eagle-import:0402")
      (libsource (lib "eagle-import") (part "C_0402"))
    )
    (comp (ref "U$6")
      (value "XTAL_16.384MHZ_CFPX-218XT")
      (footprint "eagle-import:XTAL_2.5X2.0")
      (libsource (lib "eagle-import") (part "XTAL_16.384MHZ_CFPX-218XT"))
    )
    (comp (ref "U$7")
      (value "VAR_10MM_VDRUS10")
      (footprint "eagle-import:VAR_10MM_VDRUS10")
      (libsource (lib "eagle-import") (part "VAR_10MM_VDRUS10"))
    )
    (comp (ref "U$8")
      (value "220uF")
      (footprint "eagle-import:C_AL_ELECTROLYTIC_SMD_220UF")
      (libsource (lib "eagle-import") (part "C_AL_ELECTROLYTIC_SMD_220UF"))
    )
    (comp (ref "U2")
      (value "AP2141DWG-5")
      (footprint "eagle-import:SOT-23-5")
      (libsource (lib "eagle-import") (part "AP2141DWG-5"))
    )
    (comp (ref "U3")
      (value "KSZ8081RNACAQFN-24-M")
      (footprint "eagle-import:QFN-24-M")
      (fields (field (name "MANUFACTURER_PART_NUMBER") "KSZ8081RNACA"))
      (libsource (lib "eagle-import") (part "KSZ8081RNACAQFN-24-M"))
    )
    (comp (ref "U4")
      (value "S7G2_X_176")
      (footprint "eagle-import:LQFP176_24X24")
      (libsource (lib "eagle-import") (part "S7G2_X_176"))
    )
    (comp (ref "U6")
      (value "ATM90E36A-AU-YTQFP48-M")
      (footprint "eagle-import:TQFP48-M")
      (fields (field (name "MANUFACTURER_PART_NUMBER") "ATM90E36AAUY"))
      (libsource (lib "eagle-import") (part "ATM90E36A-AU-YTQFP48-M"))
    )
    (comp (ref "U7")
      (value "TMLM_04109")
      (footprint "eagle-import:TMLM04")
      (libsource (lib "eagle-import") (part "TMLM_04109"))
    )
    (comp (ref "X3")
      (value "32.768KHZ")
      (footprint "eagle-import:SMD_X_2_PADS")
      (libsource (lib "eagle-import") (part "XTAL_32.768KHZ"))
    )
    (comp (ref "X4")
      (value "24MHZ")
      (footprint "eagle-import:SMD_3225")
      (libsource (lib "eagle-import") (part "XTAL_24_MHZ"))
    )
  )
  (nets
    (net (code "1") (name "BUSY") (class "Default")
      (node (ref "U$1") (pin "P$8") (pinfunction "P$8_P$8") (pintype "bidirectional"))
    )
    (net (code "2") (name "C58") (class "Default")
      (node (ref "C39") (pin "P$1") (pinfunction "1_P$1") (pintype "passive"))
      (node (ref "J4") (pin "4") (pinfunction "CT1_4") (pintype "bidirectional"))
    )
    (net (code "3") (name "C60") (class "Default")
      (node (ref "C40") (pin "P$1") (pinfunction "1_P$1") (pintype "passive"))
      (node (ref "J4") (pin "5") (pinfunction "CT2_5") (pintype "bidirectional"))
    )
    (net (code "4") (name "CF1") (class "Default")
      (node (ref "U6") (pin "25") (pinfunction "CF1_25") (pintype "output"))
    )
    (net (code "5") (name "CF2") (class "Default")
      (node (ref "U6") (pin "26") (pinfunction "CF2_26") (pintype "output"))
    )
    (net (code "6") (name "CF3") (class "Default")
      (node (ref "U6") (pin "27") (pinfunction "CF3_27") (pintype "output"))
    )
    (net (code "7") (name "CF4") (class "Default")
      (node (ref "U6") (pin "28") (pinfunction "CF4_28") (pintype "output"))
    )
    (net (code "8") (name "CRS_DV") (class "Default")
      (node (ref "R33") (pin "P$2") (pinfunction "2_P$2") (pintype "passive"))
      (node (ref "U3") (pin "15") (pinfunction "CRS_DV/PHYAD[1:0]_15") (pintype "bidirectional"))
    )
    (net (code "9") (name "DMA") (class "Default")
      (node (ref "U6") (pin "36") (pinfunction "DMA_CTRL_36") (pintype "input"))
    )
    (net (code "10") (name "ETH") (class "Default")
      (node (ref "U3") (pin "16") (pinfunction "REF_CLK_16") (pintype "bidirectional"))
      (node (ref "U4") (pin "9") (pinfunction "P7_1_9") (pintype "bidirectional"))
    )
    (net (code "11") (name "ETH_CRS_DV") (class "Default")
      (node (ref "R33") (pin "P$1") (pinfunction "1_P$1") (pintype "passive"))
      (node (ref "U4") (pin "13") (pinfunction "P7_5_13") (pintype "bidirectional"))
    )
    (net (code "12") (name "ETH_IRQ14") (class "Default")
      (node (ref "R26") (pin "P$1") (pinfunction "1_P$1") (pintype "passive"))
      (node (ref "U3") (pin "18") (pinfunction "INTRP_18") (pintype "bidirectional"))
      (node (ref "U4") (pin "159") (pinfunction "P0_10/AN103_159") (pintype "bidirectional"))
    )
    (net (code "13") (name "ETH_MDC") (class "Default")
      (node (ref "R28") (pin "P$1") (pinfunction "1_P$1") (pintype "passive"))
      (node (ref "U3") (pin "11") (pinfunction "MDC_11") (pintype "input"))
      (node (ref "U4") (pin "4") (pinfunction "P4_3_4") (pintype "bidirectional"))
    )
    (net (code "14") (name "ETH_MDIO") (class "Default")
      (node (ref "R29") (pin "P$1") (pinfunction "1_P$1") (pintype "passive"))
      (node (ref "U3") (pin "10") (pinfunction "MDIO_10") (pintype "bidirectional"))
      (node (ref "U4") (pin "5") (pinfunction "P4_4_5") (pintype "bidirectional"))
    )
    (net (code "15") (name "ETH_RESET") (class "Default")
      (node (ref "R27") (pin "P$1") (pinfunction "1_P$1") (pintype "passive"))
      (node (ref "U$4") (pin "P$1") (pinfunction "1_P$1") (pintype "passive"))
      (node (ref "U3") (pin "24") (pinfunction "~{RST}_24") (pintype "input"))
      (node (ref "U4") (pin "172") (pinfunction "P8_6_172") (pintype "bidirectional"))
    )
    (net (code "16") (name "ETH_RXD0") (class "Default")
      (node (ref "R31") (pin "P$1") (pinfunction "1_P$1") (pintype "passive"))
      (node (ref "U4") (pin "10") (pinfunction "P7_2_10") (pintype "bidirectional"))
    )
    (net (code "17") (name "ETH_RXD1") (class "Default")
      (node (ref "R30") (pin "P$1") (pinfunction "1_P$1") (pintype "passive"))
      (node (ref "U4") (pin "11") (pinfunction "P7_3_11") (pintype "bidirectional"))
    )
    (net (code "18") (name "ETH_RX_ER") (class "Default")
      (node (ref "R32") (pin "P$1") (pinfunction "1_P$1") (pintype "passive"))
      (node (ref "U4") (pin "12") (pinfunction "P7_4_12") (pintype "bidirectional"))
    )
    (net (code "19") (name "ETH_TXD0") (class "Default")
      (node (ref "U3") (pin "20") (pinfunction "TXD0_20") (pintype "input"))
      (node (ref "U4") (pin "8") (pinfunction "P7_0_8") (pintype "bidirectional"))
    )
    (net (code "20") (name "ETH_TXD1") (class "Default")
      (node (ref "U3") (pin "21") (pinfunction "TXD1_21") (pintype "bidirectional"))
      (node (ref "U4") (pin "7") (pinfunction "P4_6_7") (pintype "bidirectional"))
    )
    (net (code "21") (name "ETH_TXD_EN") (class "Default")
      (node (ref "U3") (pin "19") (pinfunction "TXEN_19") (pintype "input"))
      (node (ref "U4") (pin "6") (pinfunction "P4_5_6") (pintype "bidirectional"))
    )
    (net (code "22") (name "GND") (class "Default")
      (node (ref "C1") (pin "P$1") (pinfunction "1_P$1") (pintype "passive"))
      (node (ref "C10") (pin "P$1") (pinfunction "1_P$1") (pintype "passive"))
      (node (ref "C100") (pin "P$2") (pinfunction "2_P$2") (pintype "passive"))
      (node (ref "C101") (pin "2") (pinfunction "2_2") (pintype "passive"))
      (node (ref "C11") (pin "P$2") (pinfunction "2_P$2") (pintype "passive"))
      (node (ref "C13") (pin "P$1") (pinfunction "1_P$1") (pintype "passive"))
      (node (ref "C14") (pin "P$1") (pinfunction "1_P$1") (pintype "passive"))
      (node (ref "C15") (pin "2") (pinfunction "2_2") (pintype "passive"))
      (node (ref "C16") (pin "P$2") (pinfunction "2_P$2") (pintype "passive"))
      (node (ref "C2") (pin "P$1") (pinfunction "1_P$1") (pintype "passive"))
      (node (ref "C30") (pin "P$1") (pinfunction "1_P$1") (pintype "passive"))
      (node (ref "C31") (pin "P$2") (pinfunction "2_P$2") (pintype "passive"))
      (node (ref "C32") (pin "P$2") (pinfunction "2_P$2") (pintype "passive"))
      (node (ref "C36") (pin "P$1") (pinfunction "1_P$1") (pintype "passive"))
      (node (ref "C37") (pin "P$1") (pinfunction "1_P$1") (pintype "passive"))
      (node (ref "C38") (pin "P$2") (pinfunction "2_P$2") (pintype "passive"))
      (node (ref "C39") (pin "P$2") (pinfunction "2_P$2") (pintype "passive"))
      (node (ref "C40") (pin "P$2") (pinfunction "2_P$2") (pintype "passive"))
      (node (ref "C41") (pin "P$2") (pinfunction "2_P$2") (pintype "passive"))
      (node (ref "C42") (pin "P$2") (pinfunction "2_P$2") (pintype "passive"))
      (node (ref "C43") (pin "2") (pinfunction "2_2") (pintype "passive"))
      (node (ref "C44") (pin "P$2") (pinfunction "2_P$2") (pintype "passive"))
      (node (ref "C45") (pin "P$2") (pinfunction "2_P$2") (pintype "passive"))
      (node (ref "C46") (pin "P$2") (pinfunction "2_P$2") (pintype "passive"))
      (node (ref "C47") (pin "P$2") (pinfunction "2_P$2") (pintype "passive"))
      (node (ref "C48") (pin "2") (pinfunction "2_2") (pintype "passive"))
      (node (ref "C49") (pin "P$2") (pinfunction "2_P$2") (pintype "passive"))
      (node (ref "C5") (pin "P$2") (pinfunction "2_P$2") (pintype "passive"))
      (node (ref "C50") (pin "P$2") (pinfunction "2_P$2") (pintype "passive"))
      (node (ref "C51") (pin "P$2") (pinfunction "2_P$2") (pintype "passive"))
      (node (ref "C52") (pin "P$2") (pinfunction "2_P$2") (pintype "passive"))
      (node (ref "C53") (pin "P$2") (pinfunction "2_P$2") (pintype "passive"))
      (node (ref "C54") (pin "P$1") (pinfunction "1_P$1") (pintype "passive"))
      (node (ref "C55") (pin "P$1") (pinfunction "1_P$1") (pintype "passive"))
      (node (ref "C56") (pin "P$1") (pinfunction "1_P$1") (pintype "passive"))
      (node (ref "C57") (pin "P$2") (pinfunction "2_P$2") (pintype "passive"))
      (node (ref "C58") (pin "P$2") (pinfunction "2_P$2") (pintype "passive"))
      (node (ref "C59") (pin "P$2") (pinfunction "2_P$2") (pintype "passive"))
      (node (ref "C60") (pin "P$2") (pinfunction "2_P$2") (pintype "passive"))
      (node (ref "C61") (pin "P$1") (pinfunction "1_P$1") (pintype "passive"))
      (node (ref "C71") (pin "P$2") (pinfunction "2_P$2") (pintype "passive"))
      (node (ref "C72") (pin "P$1") (pinfunction "1_P$1") (pintype "passive"))
      (node (ref "C73") (pin "P$2") (pinfunction "2_P$2") (pintype "passive"))
      (node (ref "C74") (pin "P$1") (pinfunction "1_P$1") (pintype "passive"))
      (node (ref "C75") (pin "P$2") (pinfunction "2_P$2") (pintype "passive"))
      (node (ref "C76") (pin "P$1") (pinfunction "1_P$1") (pintype "passive"))
      (node (ref "C77") (pin "P$2") (pinfunction "2_P$2") (pintype "passive"))
      (node (ref "C78") (pin "P$1") (pinfunction "1_P$1") (pintype "passive"))
      (node (ref "C79") (pin "P$1") (pinfunction "1_P$1") (pintype "passive"))
      (node (ref "C8") (pin "P$2") (pinfunction "2_P$2") (pintype "passive"))
      (node (ref "C80") (pin "P$1") (pinfunction "1_P$1") (pintype "passive"))
      (node (ref "C81") (pin "P$1") (pinfunction "1_P$1") (pintype "passive"))
      (node (ref "C82") (pin "P$1") (pinfunction "1_P$1") (pintype "passive"))
      (node (ref "C83") (pin "P$1") (pinfunction "1_P$1") (pintype "passive"))
      (node (ref "C84") (pin "P$1") (pinfunction "1_P$1") (pintype "passive"))
      (node (ref "C85") (pin "P$2") (pinfunction "2_P$2") (pintype "passive"))
      (node (ref "C86") (pin "P$2") (pinfunction "2_P$2") (pintype "passive"))
      (node (ref "C87") (pin "P$1") (pinfunction "1_P$1") (pintype "passive"))
      (node (ref "C88") (pin "P$1") (pinfunction "1_P$1") (pintype "passive"))
      (node (ref "C89") (pin "P$2") (pinfunction "2_P$2") (pintype "passive"))
      (node (ref "C90") (pin "P$2") (pinfunction "2_P$2") (pintype "passive"))
      (node (ref "C91") (pin "P$2") (pinfunction "2_P$2") (pintype "passive"))
      (node (ref "C92") (pin "P$2") (pinfunction "2_P$2") (pintype "passive"))
      (node (ref "C93") (pin "P$2") (pinfunction "P$2_P$2") (pintype "bidirectional"))
      (node (ref "C94") (pin "P$2") (pinfunction "2_P$2") (pintype "passive"))
      (node (ref "C95") (pin "P$2") (pinfunction "2_P$2") (pintype "passive"))
      (node (ref "C96") (pin "2") (pinfunction "2_2") (pintype "passive"))
      (node (ref "C97") (pin "P$2") (pinfunction "2_P$2") (pintype "passive"))
      (node (ref "C98") (pin "P$2") (pinfunction "2_P$2") (pintype "passive"))
      (node (ref "C99") (pin "2") (pinfunction "2_2") (pintype "passive"))
      (node (ref "IC3") (pin "2") (pinfunction "GND_2") (pintype "power_in"))
      (node (ref "IC4") (pin "2") (pinfunction "GND_2") (pintype "power_in"))
      (node (ref "J10") (pin "P$2") (pinfunction "P$2_P$2") (pintype "bidirectional"))
      (node (ref "J11") (pin "10") (pinfunction "10_10") (pintype "passive"))
      (node (ref "J11") (pin "6") (pinfunction "6_6") (pintype "passive"))
      (node (ref "J11") (pin "8") (pinfunction "8_8") (pintype "passive"))
      (node (ref "J2") (pin "P$5") (pinfunction "GND_P$5") (pintype "bidirectional"))
      (node (ref "J3") (pin "GND") (pinfunction "GND_GND") (pintype "power_in"))
      (node (ref "J4") (pin "10") (pinfunction "GLO_10") (pintype "bidirectional"))
      (node (ref "J4") (pin "8") (pinfunction "P8_8") (pintype "bidirectional"))
      (node (ref "LED3") (pin "C") (pinfunction "C_C") (pintype "passive"))
      (node (ref "LED4") (pin "C") (pinfunction "C_C") (pintype "passive"))
      (node (ref "R107") (pin "P$2") (pinfunction "2_P$2") (pintype "passive"))
      (node (ref "R108") (pin "P$2") (pinfunction "2_P$2") (pintype "passive"))
      (node (ref "R116") (pin "P$2") (pinfunction "2_P$2") (pintype "passive"))
      (node (ref "R117") (pin "P$2") (pinfunction "2_P$2") (pintype "passive"))
      (node (ref "R125") (pin "P$2") (pinfunction "2_P$2") (pintype "passive"))
      (node (ref "R126") (pin "P$2") (pinfunction "2_P$2") (pintype "passive"))
      (node (ref "R16") (pin "P$1") (pinfunction "1_P$1") (pintype "passive"))
      (node (ref "R17") (pin "P$1") (pinfunction "1_P$1") (pintype "passive"))
      (node (ref "R19") (pin "P$1") (pinfunction "1_P$1") (pintype "passive"))
      (node (ref "R25") (pin "P$1") (pinfunction "1_P$1") (pintype "passive"))
      (node (ref "R7") (pin "P$1") (pinfunction "1_P$1") (pintype "passive"))
      (node (ref "R77") (pin "P$1") (pinfunction "1_P$1") (pintype "passive"))
      (node (ref "R80") (pin "P$1") (pinfunction "1_P$1") (pintype "passive"))
      (node (ref "R83") (pin "P$1") (pinfunction "1_P$1") (pintype "passive"))
      (node (ref "R86") (pin "P$1") (pinfunction "1_P$1") (pintype "passive"))
      (node (ref "R89") (pin "P$1") (pinfunction "1_P$1") (pintype "passive"))
      (node (ref "R92") (pin "P$1") (pinfunction "1_P$1") (pintype "passive"))
      (node (ref "R95") (pin "P$1") (pinfunction "1_P$1") (pintype "passive"))
      (node (ref "R98") (pin "P$1") (pinfunction "1_P$1") (pintype "passive"))
      (node (ref "U$1") (pin "P$3") (pinfunction "P$3_P$3") (pintype "bidirectional"))
      (node (ref "U$3") (pin "2") (pinfunction "2_2") (pintype "bidirectional"))
      (node (ref "U$3") (pin "4") (pinfunction "4_4") (pintype "bidirectional"))
      (node (ref "U$4") (pin "P$2") (pinfunction "2_P$2") (pintype "passive"))
      (node (ref "U$6") (pin "2") (pinfunction "2_2") (pintype "bidirectional"))
      (node (ref "U$6") (pin "4") (pinfunction "4_4") (pintype "bidirectional"))
      (node (ref "U$7") (pin "P$2") (pinfunction "P$2_P$2") (pintype "bidirectional"))
      (node (ref "U$8") (pin "N-") (pinfunction "-_N-") (pintype "passive"))
      (node (ref "U2") (pin "2") (pinfunction "GND_2") (pintype "input"))
      (node (ref "U3") (pin "22") (pinfunction "GND_22") (pintype "power_in"))
      (node (ref "U3") (pin "25") (pinfunction "25_25") (pintype "passive"))
      (node (ref "U4") (pin "111") (pinfunction "VSS(IO)5_111") (pintype "bidirectional"))
      (node (ref "U4") (pin "124") (pinfunction "VSS(IO)6_124") (pintype "bidirectional"))
      (node (ref "U4") (pin "139") (pinfunction "VSS(IO)7_139") (pintype "bidirectional"))
      (node (ref "U4") (pin "150") (pinfunction "VSS(IO)8_150") (pintype "bidirectional"))
      (node (ref "U4") (pin "153") (pinfunction "VREFL_153") (pintype "bidirectional"))
      (node (ref "U4") (pin "156") (pinfunction "AVSS0_156") (pintype "bidirectional"))
      (node (ref "U4") (pin "157") (pinfunction "VREFL0_157") (pintype "bidirectional"))
      (node (ref "U4") (pin "170") (pinfunction "VSS(IO)9_170") (pintype "bidirectional"))
      (node (ref "U4") (pin "22") (pinfunction "VSS1_22") (pintype "bidirectional"))
      (node (ref "U4") (pin "28") (pinfunction "AVSS_USBHS_28") (pintype "bidirectional"))
      (node (ref "U4") (pin "29") (pinfunction "PVSS_USBHS_29") (pintype "bidirectional"))
      (node (ref "U4") (pin "30") (pinfunction "VSS2_USBHS_30") (pintype "bidirectional"))
      (node (ref "U4") (pin "33") (pinfunction "VSS1_USBHS_33") (pintype "bidirectional"))
      (node (ref "U4") (pin "35") (pinfunction "VSSIO_35") (pintype "bidirectional"))
      (node (ref "U4") (pin "45") (pinfunction "VSS_USB_45") (pintype "bidirectional"))
      (node (ref "U4") (pin "60") (pinfunction "VSS(IO)2_60") (pintype "bidirectional"))
      (node (ref "U4") (pin "63") (pinfunction "VSS(IO/DCDC)_63") (pintype "bidirectional"))
      (node (ref "U4") (pin "66") (pinfunction "VCC_DCDC(IO/DCDC)_66") (pintype "bidirectional"))
      (node (ref "U4") (pin "83") (pinfunction "VSS(IO)3_83") (pintype "bidirectional"))
      (node (ref "U4") (pin "98") (pinfunction "VSS(IO)4_98") (pintype "bidirectional"))
      (node (ref "U6") (pin "12") (pinfunction "AGND_12") (pintype "power_in"))
      (node (ref "U6") (pin "19") (pinfunction "DGND_2_19") (pintype "power_in"))
      (node (ref "U6") (pin "2") (pinfunction "AGND_2_2") (pintype "power_in"))
      (node (ref "U6") (pin "32") (pinfunction "TEST_32") (pintype "input"))
      (node (ref "U6") (pin "44") (pinfunction "DGND_3_44") (pintype "power_in"))
      (node (ref "U6") (pin "47") (pinfunction "DGND_47") (pintype "power_in"))
      (node (ref "U7") (pin "P$3") (pinfunction "VOUT-_P$3") (pintype "bidirectional"))
      (node (ref "U7") (pin "P$6") (pinfunction "AC_N_P$6") (pintype "bidirectional"))
      (node (ref "X4") (pin "2") (pinfunction "2_2") (pintype "bidirectional"))
      (node (ref "X4") (pin "4") (pinfunction "4_4") (pintype "bidirectional"))
    )
    (net (code "23") (name "GNDE") (class "Default")
      (node (ref "J2") (pin "P$6") (pinfunction "SHIELD1_P$6") (pintype "bidirectional"))
      (node (ref "J2") (pin "P$7") (pinfunction "SHIELD2_P$7") (pintype "bidirectional"))
      (node (ref "J2") (pin "P$8") (pinfunction "SHIELD3_P$8") (pintype "bidirectional"))
      (node (ref "J2") (pin "P$9") (pinfunction "SHIELD4_P$9") (pintype "bidirectional"))
      (node (ref "J3") (pin "SHLD1") (pinfunction "SHIELD_1_SHLD1") (pintype "bidirectional"))
      (node (ref "J3") (pin "SHLD2") (pinfunction "SHIELD_2_SHLD2") (pintype "bidirectional"))
      (node (ref "J4") (pin "13") (pinfunction "GNDE0_13") (pintype "bidirectional"))
      (node (ref "J4") (pin "14") (pinfunction "GNDE1_14") (pintype "bidirectional"))
    )
    (net (code "24") (name "GP4") (class "Default")
      (node (ref "U4") (pin "49") (pinfunction "P2_7_49") (pintype "bidirectional"))
    )
    (net (code "25") (name "IAN") (class "Default")
      (node (ref "C72") (pin "P$2") (pinfunction "2_P$2") (pintype "passive"))
      (node (ref "R81") (pin "P$2") (pinfunction "2_P$2") (pintype "passive"))
      (node (ref "U6") (pin "4") (pinfunction "I1N_4") (pintype "input"))
    )
    (net (code "26") (name "IAP") (class "Default")
      (node (ref "C71") (pin "P$1") (pinfunction "1_P$1") (pintype "passive"))
      (node (ref "R78") (pin "P$1") (pinfunction "1_P$1") (pintype "passive"))
      (node (ref "U6") (pin "3") (pinfunction "I1P_3") (pintype "input"))
    )
    (net (code "27") (name "IA_1+") (class "Default")
      (node (ref "J5") (pin "P$1") (pinfunction "P$1_P$1") (pintype "bidirectional"))
      (node (ref "R76") (pin "P$1") (pinfunction "1_P$1") (pintype "passive"))
    )
    (net (code "28") (name "IA_2-") (class "Default")
      (node (ref "J5") (pin "P$2") (pinfunction "P$2_P$2") (pintype "bidirectional"))
      (node (ref "R79") (pin "P$2") (pinfunction "2_P$2") (pintype "passive"))
    )
    (net (code "29") (name "IBN") (class "Default")
      (node (ref "C74") (pin "P$2") (pinfunction "2_P$2") (pintype "passive"))
      (node (ref "R87") (pin "P$2") (pinfunction "2_P$2") (pintype "passive"))
      (node (ref "U6") (pin "6") (pinfunction "I2N_6") (pintype "input"))
    )
    (net (code "30") (name "IBP") (class "Default")
      (node (ref "C73") (pin "P$1") (pinfunction "1_P$1") (pintype "passive"))
      (node (ref "R84") (pin "P$1") (pinfunction "1_P$1") (pintype "passive"))
      (node (ref "U6") (pin "5") (pinfunction "I2P_5") (pintype "input"))
    )
    (net (code "31") (name "IB_1+") (class "Default")
      (node (ref "J5") (pin "P$3") (pinfunction "P$3_P$3") (pintype "bidirectional"))
      (node (ref "R82") (pin "P$1") (pinfunction "1_P$1") (pintype "passive"))
    )
    (net (code "32") (name "IB_2-") (class "Default")
      (node (ref "J5") (pin "P$4") (pinfunction "P$4_P$4") (pintype "bidirectional"))
      (node (ref "R85") (pin "P$2") (pinfunction "2_P$2") (pintype "passive"))
    )
    (net (code "33") (name "ICN") (class "Default")
      (node (ref "C76") (pin "P$2") (pinfunction "2_P$2") (pintype "passive"))
      (node (ref "R93") (pin "P$2") (pinfunction "2_P$2") (pintype "passive"))
      (node (ref "U6") (pin "8") (pinfunction "I3N_8") (pintype "input"))
    )
    (net (code "34") (name "ICP") (class "Default")
      (node (ref "C75") (pin "P$1") (pinfunction "1_P$1") (pintype "passive"))
      (node (ref "R90") (pin "P$1") (pinfunction "1_P$1") (pintype "passive"))
      (node (ref "U6") (pin "7") (pinfunction "I3P_7") (pintype "input"))
    )
    (net (code "35") (name "IC_1+") (class "Default")
      (node (ref "J1") (pin "P$1") (pinfunction "P$1_P$1") (pintype "bidirectional"))
      (node (ref "R88") (pin "P$1") (pinfunction "1_P$1") (pintype "passive"))
    )
    (net (code "36") (name "IC_2-") (class "Default")
      (node (ref "J1") (pin "P$2") (pinfunction "P$2_P$2") (pintype "bidirectional"))
      (node (ref "R91") (pin "P$2") (pinfunction "2_P$2") (pintype "passive"))
    )
    (net (code "37") (name "ID") (class "Default")
      (node (ref "J2") (pin "P$4") (pinfunction "ID_P$4") (pintype "bidirectional"))
    )
    (net (code "38") (name "IIC_0_SCL") (class "Default")
      (node (ref "U4") (pin "1") (pinfunction "P4_0_1") (pintype "bidirectional"))
    )
    (net (code "39") (name "IIC_0_SDA") (class "Default")
      (node (ref "U4") (pin "2") (pinfunction "P4_1_2") (pintype "bidirectional"))
    )
    (net (code "40") (name "INN") (class "Default")
      (node (ref "C78") (pin "P$2") (pinfunction "2_P$2") (pintype "passive"))
      (node (ref "R99") (pin "P$2") (pinfunction "2_P$2") (pintype "passive"))
      (node (ref "U6") (pin "10") (pinfunction "I4N_10") (pintype "input"))
    )
    (net (code "41") (name "INP") (class "Default")
      (node (ref "C77") (pin "P$1") (pinfunction "1_P$1") (pintype "passive"))
      (node (ref "R96") (pin "P$1") (pinfunction "1_P$1") (pintype "passive"))
      (node (ref "U6") (pin "9") (pinfunction "I4P_9") (pintype "input"))
    )
    (net (code "42") (name "INT_AI_LS_0") (class "Default")
      (node (ref "U4") (pin "3") (pinfunction "P4_2_3") (pintype "bidirectional"))
    )
    (net (code "43") (name "INT_AI_LS_1") (class "Default")
      (node (ref "U4") (pin "43") (pinfunction "P4_8_43") (pintype "bidirectional"))
    )
    (net (code "44") (name "INT_MI_01") (class "Default")
      (node (ref "U4") (pin "87") (pinfunction "P3_1_87") (pintype "bidirectional"))
    )
    (net (code "45") (name "INT_MI_02") (class "Default")
      (node (ref "U4") (pin "86") (pinfunction "P3_2_86") (pintype "bidirectional"))
    )
    (net (code "46") (name "INT_MI_03") (class "Default")
      (node (ref "U4") (pin "128") (pinfunction "P1_4_128") (pintype "bidirectional"))
    )
    (net (code "47") (name "INT_MI_04") (class "Default")
      (node (ref "U4") (pin "127") (pinfunction "P1_5_127") (pintype "bidirectional"))
    )
    (net (code "48") (name "IN_1+") (class "Default")
      (node (ref "J1") (pin "P$3") (pinfunction "P$3_P$3") (pintype "bidirectional"))
      (node (ref "R94") (pin "P$1") (pinfunction "1_P$1") (pintype "passive"))
    )
    (net (code "49") (name "IN_2-") (class "Default")
      (node (ref "J1") (pin "P$4") (pinfunction "P$4_P$4") (pintype "bidirectional"))
      (node (ref "R97") (pin "P$2") (pinfunction "2_P$2") (pintype "passive"))
    )
    (net (code "50") (name "IRQ0") (class "Default")
      (node (ref "U6") (pin "30") (pinfunction "IRQ0_30") (pintype "output"))
    )
    (net (code "51") (name "IRQ1") (class "Default")
      (node (ref "U6") (pin "31") (pinfunction "IRQ1_31") (pintype "output"))
    )
    (net (code "52") (name "LED1{slash}SPEED") (class "Default")
      (node (ref "J4") (pin "11") (pinfunction "YLO_11") (pintype "bidirectional"))
      (node (ref "U3") (pin "23") (pinfunction "LED0/ANEN_SPEED_23") (pintype "bidirectional"))
    )
    (net (code "53") (name "M0_DIR") (class "Default")
      (node (ref "U4") (pin "39") (pinfunction "P4_12_39") (pintype "bidirectional"))
    )
    (net (code "54") (name "M0_STEP") (class "Default")
      (node (ref "U4") (pin "16") (pinfunction "PB_0_16") (pintype "bidirectional"))
    )
    (net (code "55") (name "M1_DIR") (class "Default")
      (node (ref "U4") (pin "40") (pinfunction "P4_11_40") (pintype "bidirectional"))
    )
    (net (code "56") (name "M1_STEP") (class "Default")
      (node (ref "U4") (pin "36") (pinfunction "P4_15_36") (pintype "bidirectional"))
    )
    (net (code "57") (name "M2_DIR") (class "Default")
      (node (ref "U4") (pin "41") (pinfunction "P4_10_41") (pintype "bidirectional"))
    )
    (net (code "58") (name "M2_STEP") (class "Default")
      (node (ref "U4") (pin "37") (pinfunction "P4_14_37") (pintype "bidirectional"))
    )
    (net (code "59") (name "M3_DIR") (class "Default")
      (node (ref "U4") (pin "42") (pinfunction "P4_9_42") (pintype "bidirectional"))
    )
    (net (code "60") (name "M3_STEP") (class "Default")
      (node (ref "U4") (pin "38") (pinfunction "P4_13_38") (pintype "bidirectional"))
    )
    (net (code "61") (name "NC") (class "Default")
      (node (ref "J4") (pin "7") (pinfunction "P7_7") (pintype "bidirectional"))
    )
    (net (code "62") (name "Net-(C16-1)") (class "Default")
      (node (ref "C16") (pin "P$1") (pinfunction "1_P$1") (pintype "passive"))
      (node (ref "J2") (pin "P$1") (pinfunction "VBUS_P$1") (pintype "bidirectional"))
      (node (ref "R4") (pin "P$2") (pinfunction "2_P$2") (pintype "passive"))
      (node (ref "R7") (pin "P$2") (pinfunction "2_P$2") (pintype "passive"))
    )
    (net (code "63") (name "Net-(C31-1)") (class "Default")
      (node (ref "C31") (pin "P$1") (pinfunction "1_P$1") (pintype "passive"))
      (node (ref "U4") (pin "62") (pinfunction "VCL1_62") (pintype "bidirectional"))
    )
    (net (code "64") (name "Net-(C37-2)") (class "Default")
      (node (ref "C37") (pin "P$2") (pinfunction "2_P$2") (pintype "passive"))
      (node (ref "U4") (pin "148") (pinfunction "VCL2_148") (pintype "bidirectional"))
    )
    (net (code "65") (name "Net-(C38-1)") (class "Default")
      (node (ref "C38") (pin "P$1") (pinfunction "1_P$1") (pintype "passive"))
      (node (ref "U4") (pin "19") (pinfunction "VCLO_19") (pintype "bidirectional"))
    )
    (net (code "66") (name "Net-(C44-1)") (class "Default")
      (node (ref "C43") (pin "1") (pinfunction "1_1") (pintype "passive"))
      (node (ref "C44") (pin "P$1") (pinfunction "1_P$1") (pintype "passive"))
      (node (ref "FB2/2") (pin "2") (pinfunction "P$2_2") (pintype "bidirectional"))
      (node (ref "U3") (pin "2") (pinfunction "VDDA_3.3_2") (pintype "power_in"))
    )
    (net (code "67") (name "Net-(J2-D+)") (class "Default")
      (node (ref "J2") (pin "P$3") (pinfunction "D+_P$3") (pintype "bidirectional"))
      (node (ref "R6") (pin "P$2") (pinfunction "2_P$2") (pintype "passive"))
    )
    (net (code "68") (name "Net-(J2-D-)") (class "Default")
      (node (ref "J2") (pin "P$2") (pinfunction "D-_P$2") (pintype "bidirectional"))
      (node (ref "R5") (pin "P$2") (pinfunction "2_P$2") (pintype "passive"))
    )
    (net (code "69") (name "Net-(R16-2)") (class "Default")
      (node (ref "R16") (pin "P$2") (pinfunction "2_P$2") (pintype "passive"))
      (node (ref "U4") (pin "65") (pinfunction "VLO2(DCDC)_65") (pintype "bidirectional"))
    )
    (net (code "70") (name "Net-(R17-2)") (class "Default")
      (node (ref "R17") (pin "P$2") (pinfunction "2_P$2") (pintype "passive"))
      (node (ref "U4") (pin "64") (pinfunction "VLO1(DCDC)_64") (pintype "bidirectional"))
    )
    (net (code "71") (name "Net-(R19-2)") (class "Default")
      (node (ref "R19") (pin "P$2") (pinfunction "2_P$2") (pintype "passive"))
      (node (ref "U4") (pin "27") (pinfunction "USBHS_RREF_27") (pintype "bidirectional"))
    )
    (net (code "72") (name "Net-(R76-2)") (class "Default")
      (node (ref "R76") (pin "P$2") (pinfunction "2_P$2") (pintype "passive"))
      (node (ref "R77") (pin "P$2") (pinfunction "2_P$2") (pintype "passive"))
      (node (ref "R78") (pin "P$2") (pinfunction "2_P$2") (pintype "passive"))
    )
    (net (code "73") (name "Net-(R79-1)") (class "Default")
      (node (ref "R79") (pin "P$1") (pinfunction "1_P$1") (pintype "passive"))
      (node (ref "R80") (pin "P$2") (pinfunction "2_P$2") (pintype "passive"))
      (node (ref "R81") (pin "P$1") (pinfunction "1_P$1") (pintype "passive"))
    )
    (net (code "74") (name "Net-(R82-2)") (class "Default")
      (node (ref "R82") (pin "P$2") (pinfunction "2_P$2") (pintype "passive"))
      (node (ref "R83") (pin "P$2") (pinfunction "2_P$2") (pintype "passive"))
      (node (ref "R84") (pin "P$2") (pinfunction "2_P$2") (pintype "passive"))
    )
    (net (code "75") (name "Net-(R85-1)") (class "Default")
      (node (ref "R85") (pin "P$1") (pinfunction "1_P$1") (pintype "passive"))
      (node (ref "R86") (pin "P$2") (pinfunction "2_P$2") (pintype "passive"))
      (node (ref "R87") (pin "P$1") (pinfunction "1_P$1") (pintype "passive"))
    )
    (net (code "76") (name "Net-(R88-2)") (class "Default")
      (node (ref "R88") (pin "P$2") (pinfunction "2_P$2") (pintype "passive"))
      (node (ref "R89") (pin "P$2") (pinfunction "2_P$2") (pintype "passive"))
      (node (ref "R90") (pin "P$2") (pinfunction "2_P$2") (pintype "passive"))
    )
    (net (code "77") (name "Net-(R91-1)") (class "Default")
      (node (ref "R91") (pin "P$1") (pinfunction "1_P$1") (pintype "passive"))
      (node (ref "R92") (pin "P$2") (pinfunction "2_P$2") (pintype "passive"))
      (node (ref "R93") (pin "P$1") (pinfunction "1_P$1") (pintype "passive"))
    )
    (net (code "78") (name "Net-(R94-2)") (class "Default")
      (node (ref "R94") (pin "P$2") (pinfunction "2_P$2") (pintype "passive"))
      (node (ref "R95") (pin "P$2") (pinfunction "2_P$2") (pintype "passive"))
      (node (ref "R96") (pin "P$2") (pinfunction "2_P$2") (pintype "passive"))
    )
    (net (code "79") (name "Net-(R97-1)") (class "Default")
      (node (ref "R97") (pin "P$1") (pinfunction "1_P$1") (pintype "passive"))
      (node (ref "R98") (pin "P$2") (pinfunction "2_P$2") (pintype "passive"))
      (node (ref "R99") (pin "P$1") (pinfunction "1_P$1") (pintype "passive"))
    )
    (net (code "80") (name "Net-(R100-1)") (class "Default")
      (node (ref "R100") (pin "P$1") (pinfunction "1_P$1") (pintype "passive"))
      (node (ref "R101") (pin "P$1") (pinfunction "1_P$1") (pintype "passive"))
    )
    (net (code "81") (name "Net-(R101-2)") (class "Default")
      (node (ref "R101") (pin "P$2") (pinfunction "2_P$2") (pintype "passive"))
      (node (ref "R102") (pin "P$2") (pinfunction "2_P$2") (pintype "passive"))
    )
    (net (code "82") (name "Net-(R102-1)") (class "Default")
      (node (ref "R102") (pin "P$1") (pinfunction "1_P$1") (pintype "passive"))
      (node (ref "R103") (pin "P$1") (pinfunction "1_P$1") (pintype "passive"))
    )
    (net (code "83") (name "Net-(R103-2)") (class "Default")
      (node (ref "R103") (pin "P$2") (pinfunction "2_P$2") (pintype "passive"))
      (node (ref "R104") (pin "P$2") (pinfunction "2_P$2") (pintype "passive"))
    )
    (net (code "84") (name "Net-(R104-1)") (class "Default")
      (node (ref "R104") (pin "P$1") (pinfunction "1_P$1") (pintype "passive"))
      (node (ref "R105") (pin "P$1") (pinfunction "1_P$1") (pintype "passive"))
    )
    (net (code "85") (name "Net-(R105-2)") (class "Default")
      (node (ref "R105") (pin "P$2") (pinfunction "2_P$2") (pintype "passive"))
      (node (ref "R106") (pin "P$2") (pinfunction "2_P$2") (pintype "passive"))
    )
    (net (code "86") (name "Net-(R109-1)") (class "Default")
      (node (ref "R109") (pin "P$1") (pinfunction "1_P$1") (pintype "passive"))
      (node (ref "R110") (pin "P$1") (pinfunction "1_P$1") (pintype "passive"))
    )
    (net (code "87") (name "Net-(R110-2)") (class "Default")
      (node (ref "R110") (pin "P$2") (pinfunction "2_P$2") (pintype "passive"))
      (node (ref "R111") (pin "P$2") (pinfunction "2_P$2") (pintype "passive"))
    )
    (net (code "88") (name "Net-(R111-1)") (class "Default")
      (node (ref "R111") (pin "P$1") (pinfunction "1_P$1") (pintype "passive"))
      (node (ref "R112") (pin "P$1") (pinfunction "1_P$1") (pintype "passive"))
    )
    (net (code "89") (name "Net-(R112-2)") (class "Default")
      (node (ref "R112") (pin "P$2") (pinfunction "2_P$2") (pintype "passive"))
      (node (ref "R113") (pin "P$2") (pinfunction "2_P$2") (pintype "passive"))
    )
    (net (code "90") (name "Net-(R113-1)") (class "Default")
      (node (ref "R113") (pin "P$1") (pinfunction "1_P$1") (pintype "passive"))
      (node (ref "R114") (pin "P$1") (pinfunction "1_P$1") (pintype "passive"))
    )
    (net (code "91") (name "Net-(R114-2)") (class "Default")
      (node (ref "R114") (pin "P$2") (pinfunction "2_P$2") (pintype "passive"))
      (node (ref "R115") (pin "P$2") (pinfunction "2_P$2") (pintype "passive"))
    )
    (net (code "92") (name "Net-(R118-1)") (class "Default")
      (node (ref "R118") (pin "P$1") (pinfunction "1_P$1") (pintype "passive"))
      (node (ref "R119") (pin "P$1") (pinfunction "1_P$1") (pintype "passive"))
    )
    (net (code "93") (name "Net-(R119-2)") (class "Default")
      (node (ref "R119") (pin "P$2") (pinfunction "2_P$2") (pintype "passive"))
      (node (ref "R120") (pin "P$2") (pinfunction "2_P$2") (pintype "passive"))
    )
    (net (code "94") (name "Net-(R120-1)") (class "Default")
      (node (ref "R120") (pin "P$1") (pinfunction "1_P$1") (pintype "passive"))
      (node (ref "R121") (pin "P$1") (pinfunction "1_P$1") (pintype "passive"))
    )
    (net (code "95") (name "Net-(R121-2)") (class "Default")
      (node (ref "R121") (pin "P$2") (pinfunction "2_P$2") (pintype "passive"))
      (node (ref "R122") (pin "P$2") (pinfunction "2_P$2") (pintype "passive"))
    )
    (net (code "96") (name "Net-(R122-1)") (class "Default")
      (node (ref "R122") (pin "P$1") (pinfunction "1_P$1") (pintype "passive"))
      (node (ref "R123") (pin "P$1") (pinfunction "1_P$1") (pintype "passive"))
    )
    (net (code "97") (name "Net-(R123-2)") (class "Default")
      (node (ref "R123") (pin "P$2") (pinfunction "2_P$2") (pintype "passive"))
      (node (ref "R124") (pin "P$2") (pinfunction "2_P$2") (pintype "passive"))
    )
    (net (code "98") (name "Net-(R128-2)") (class "Default")
      (node (ref "LED3") (pin "A") (pinfunction "A_A") (pintype "passive"))
      (node (ref "R128") (pin "P$2") (pinfunction "2_P$2") (pintype "passive"))
    )
    (net (code "99") (name "Net-(R129-2)") (class "Default")
      (node (ref "LED4") (pin "A") (pinfunction "A_A") (pintype "passive"))
      (node (ref "R129") (pin "P$2") (pinfunction "2_P$2") (pintype "passive"))
    )
    (net (code "100") (name "OSCI") (class "Default")
      (node (ref "U$6") (pin "1") (pinfunction "1_1") (pintype "bidirectional"))
      (node (ref "U6") (pin "20") (pinfunction "OSCI_20") (pintype "input"))
    )
    (net (code "101") (name "OSCO") (class "Default")
      (node (ref "U$6") (pin "3") (pinfunction "3_3") (pintype "bidirectional"))
      (node (ref "U6") (pin "21") (pinfunction "OSCO_21") (pintype "output"))
    )
    (net (code "102") (name "P0_00") (class "Default")
      (node (ref "U4") (pin "169") (pinfunction "P0_0/AN0\\00_169") (pintype "bidirectional"))
    )
    (net (code "103") (name "P0_01") (class "Default")
      (node (ref "U4") (pin "168") (pinfunction "P0_1/AN001_168") (pintype "bidirectional"))
    )
    (net (code "104") (name "P0_02") (class "Default")
      (node (ref "U4") (pin "167") (pinfunction "P0_2/AN002_167") (pintype "bidirectional"))
    )
    (net (code "105") (name "P0_03") (class "Default")
      (node (ref "U4") (pin "166") (pinfunction "P0_3/PGAVSS000_166") (pintype "bidirectional"))
    )
    (net (code "106") (name "P0_04") (class "Default")
      (node (ref "U4") (pin "165") (pinfunction "P0_4/AN100_165") (pintype "bidirectional"))
    )
    (net (code "107") (name "P0_05") (class "Default")
      (node (ref "U4") (pin "164") (pinfunction "P0_5/AN101_164") (pintype "bidirectional"))
    )
    (net (code "108") (name "P0_06") (class "Default")
      (node (ref "U4") (pin "163") (pinfunction "P0_6/AN102_163") (pintype "bidirectional"))
    )
    (net (code "109") (name "P0_07") (class "Default")
      (node (ref "U4") (pin "162") (pinfunction "P0_7/PGVSS100_162") (pintype "bidirectional"))
    )
    (net (code "110") (name "P0_08") (class "Default")
      (node (ref "U4") (pin "161") (pinfunction "P0_8/AN003_161") (pintype "bidirectional"))
    )
    (net (code "111") (name "P0_09") (class "Default")
      (node (ref "U4") (pin "160") (pinfunction "P0_9/AN004_160") (pintype "bidirectional"))
    )
    (net (code "112") (name "P0_14") (class "Default")
      (node (ref "U4") (pin "152") (pinfunction "P0_14/DA0/AN005/AN105_152") (pintype "bidirectional"))
    )
    (net (code "113") (name "P0_15") (class "Default")
      (node (ref "U4") (pin "151") (pinfunction "P0_15/DA1/AN006/AN106_151") (pintype "bidirectional"))
    )
    (net (code "114") (name "P1_06") (class "Default")
      (node (ref "U4") (pin "126") (pinfunction "P1_6_126") (pintype "bidirectional"))
    )
    (net (code "115") (name "P1_07") (class "Default")
      (node (ref "U4") (pin "125") (pinfunction "P1_7_125") (pintype "bidirectional"))
    )
    (net (code "116") (name "P1_11") (class "Default")
      (node (ref "U4") (pin "92") (pinfunction "P1_11_92") (pintype "bidirectional"))
    )
    (net (code "117") (name "P1_12") (class "Default")
      (node (ref "U4") (pin "93") (pinfunction "P1_12_93") (pintype "bidirectional"))
    )
    (net (code "118") (name "P1_13") (class "Default")
      (node (ref "U4") (pin "94") (pinfunction "P1_13_94") (pintype "bidirectional"))
    )
    (net (code "119") (name "P1_14") (class "Default")
      (node (ref "U4") (pin "95") (pinfunction "P1_14_95") (pintype "bidirectional"))
    )
    (net (code "120") (name "P1_15") (class "Default")
      (node (ref "U4") (pin "96") (pinfunction "P1_15_96") (pintype "bidirectional"))
    )
    (net (code "121") (name "P2_00") (class "Default")
      (node (ref "U4") (pin "69") (pinfunction "P2_0(INPUT_ONLY)_69") (pintype "bidirectional"))
    )
    (net (code "122") (name "P2_01") (class "Default")
      (node (ref "U4") (pin "68") (pinfunction "P2_1/MD_68") (pintype "bidirectional"))
    )
    (net (code "123") (name "P3_03") (class "Default")
      (node (ref "U4") (pin "85") (pinfunction "P3_3_85") (pintype "bidirectional"))
    )
    (net (code "124") (name "P3_04") (class "Default")
      (node (ref "U4") (pin "82") (pinfunction "P3_4_82") (pintype "bidirectional"))
    )
    (net (code "125") (name "P3_05") (class "Default")
      (node (ref "U4") (pin "81") (pinfunction "P3_5_81") (pintype "bidirectional"))
    )
    (net (code "126") (name "P3_06") (class "Default")
      (node (ref "U4") (pin "80") (pinfunction "P3_6_80") (pintype "bidirectional"))
    )
    (net (code "127") (name "P3_07") (class "Default")
      (node (ref "U4") (pin "79") (pinfunction "P3_7_79") (pintype "bidirectional"))
    )
    (net (code "128") (name "P3_09") (class "Default")
      (node (ref "U4") (pin "77") (pinfunction "P3_9_77") (pintype "bidirectional"))
    )
    (net (code "129") (name "P3_10") (class "Default")
      (node (ref "U4") (pin "76") (pinfunction "P3_10_76") (pintype "bidirectional"))
    )
    (net (code "130") (name "P3_11") (class "Default")
      (node (ref "U4") (pin "75") (pinfunction "P3_11_75") (pintype "bidirectional"))
    )
    (net (code "131") (name "P3_12") (class "Default")
      (node (ref "U4") (pin "74") (pinfunction "P3_12_74") (pintype "bidirectional"))
    )
    (net (code "132") (name "P5_11") (class "Default")
      (node (ref "U4") (pin "176") (pinfunction "P5_11_176") (pintype "bidirectional"))
    )
    (net (code "133") (name "P5_12") (class "Default")
      (node (ref "U4") (pin "175") (pinfunction "P5_12_175") (pintype "bidirectional"))
    )
    (net (code "134") (name "P5_13") (class "Default")
      (node (ref "U4") (pin "174") (pinfunction "P5_13_174") (pintype "bidirectional"))
    )
    (net (code "135") (name "P6_00") (class "Default")
      (node (ref "U4") (pin "122") (pinfunction "P6_0_122") (pintype "bidirectional"))
    )
    (net (code "136") (name "P6_01") (class "Default")
      (node (ref "U4") (pin "121") (pinfunction "P6_1_121") (pintype "bidirectional"))
    )
    (net (code "137") (name "P6_02") (class "Default")
      (node (ref "U4") (pin "120") (pinfunction "P6_2_120") (pintype "bidirectional"))
    )
    (net (code "138") (name "P6_03") (class "Default")
      (node (ref "U4") (pin "119") (pinfunction "P6_3_119") (pintype "bidirectional"))
    )
    (net (code "139") (name "P6_04") (class "Default")
      (node (ref "U4") (pin "118") (pinfunction "P6_4_118") (pintype "bidirectional"))
    )
    (net (code "140") (name "P6_05") (class "Default")
      (node (ref "U4") (pin "117") (pinfunction "P6_5_117") (pintype "bidirectional"))
    )
    (net (code "141") (name "P6_06") (class "Default")
      (node (ref "U4") (pin "116") (pinfunction "P6_6_116") (pintype "bidirectional"))
    )
    (net (code "142") (name "P6_07") (class "Default")
      (node (ref "U4") (pin "115") (pinfunction "P6_7_115") (pintype "bidirectional"))
    )
    (net (code "143") (name "P6_08") (class "Default")
      (node (ref "U4") (pin "99") (pinfunction "P6_8_99") (pintype "bidirectional"))
    )
    (net (code "144") (name "P6_09") (class "Default")
      (node (ref "U4") (pin "100") (pinfunction "P6_9_100") (pintype "bidirectional"))
    )
    (net (code "145") (name "P6_10") (class "Default")
      (node (ref "U4") (pin "101") (pinfunction "P6_10_101") (pintype "bidirectional"))
    )
    (net (code "146") (name "P6_11") (class "Default")
      (node (ref "U4") (pin "102") (pinfunction "P6_11_102") (pintype "bidirectional"))
    )
    (net (code "147") (name "P6_12") (class "Default")
      (node (ref "U4") (pin "103") (pinfunction "P6_12_103") (pintype "bidirectional"))
    )
    (net (code "148") (name "P6_13") (class "Default")
      (node (ref "U4") (pin "104") (pinfunction "P6_13_104") (pintype "bidirectional"))
    )
    (net (code "149") (name "P6_14") (class "Default")
      (node (ref "U4") (pin "105") (pinfunction "P6_14_105") (pintype "bidirectional"))
    )
    (net (code "150") (name "P6_15") (class "Default")
      (node (ref "U4") (pin "106") (pinfunction "P6_15_106") (pintype "bidirectional"))
    )
    (net (code "151") (name "P7_06") (class "Default")
      (node (ref "U4") (pin "14") (pinfunction "P7_6_14") (pintype "bidirectional"))
    )
    (net (code "152") (name "P7_07") (class "Default")
      (node (ref "U4") (pin "15") (pinfunction "P7_7_15") (pintype "bidirectional"))
    )
    (net (code "153") (name "P8_00") (class "Default")
      (node (ref "U4") (pin "133") (pinfunction "P8_0_133") (pintype "bidirectional"))
    )
    (net (code "154") (name "P8_01") (class "Default")
      (node (ref "U4") (pin "134") (pinfunction "P8_1_134") (pintype "bidirectional"))
    )
    (net (code "155") (name "P8_02") (class "Default")
      (node (ref "U4") (pin "135") (pinfunction "P8_2_135") (pintype "bidirectional"))
    )
    (net (code "156") (name "P8_03") (class "Default")
      (node (ref "U4") (pin "136") (pinfunction "P8_3_136") (pintype "bidirectional"))
    )
    (net (code "157") (name "P8_04") (class "Default")
      (node (ref "U4") (pin "137") (pinfunction "P8_4_137") (pintype "bidirectional"))
    )
    (net (code "158") (name "P8_05") (class "Default")
      (node (ref "U4") (pin "173") (pinfunction "P8_5_173") (pintype "bidirectional"))
    )
    (net (code "159") (name "P9_05") (class "Default")
      (node (ref "U4") (pin "73") (pinfunction "P9_5_73") (pintype "bidirectional"))
    )
    (net (code "160") (name "P9_06") (class "Default")
      (node (ref "U4") (pin "72") (pinfunction "P9_6_72") (pintype "bidirectional"))
    )
    (net (code "161") (name "P9_07") (class "Default")
      (node (ref "U4") (pin "71") (pinfunction "P9_7_71") (pintype "bidirectional"))
    )
    (net (code "162") (name "P9_08") (class "Default")
      (node (ref "U4") (pin "70") (pinfunction "P9_8_70") (pintype "bidirectional"))
    )
    (net (code "163") (name "PA_00") (class "Default")
      (node (ref "U4") (pin "114") (pinfunction "PA_0_114") (pintype "bidirectional"))
    )
    (net (code "164") (name "PA_01") (class "Default")
      (node (ref "U4") (pin "113") (pinfunction "PA_1_113") (pintype "bidirectional"))
    )
    (net (code "165") (name "PA_08") (class "Default")
      (node (ref "U4") (pin "107") (pinfunction "PA_8_107") (pintype "bidirectional"))
    )
    (net (code "166") (name "PA_09") (class "Default")
      (node (ref "U4") (pin "108") (pinfunction "PA_9_108") (pintype "bidirectional"))
    )
    (net (code "167") (name "PA_10") (class "Default")
      (node (ref "U4") (pin "109") (pinfunction "PA_10_109") (pintype "bidirectional"))
    )
    (net (code "168") (name "PM0") (class "Default")
      (node (ref "U6") (pin "33") (pinfunction "PM0_33") (pintype "input"))
    )
    (net (code "169") (name "PM1") (class "Default")
      (node (ref "U6") (pin "34") (pinfunction "PM1_34") (pintype "input"))
    )
    (net (code "170") (name "R51") (class "Default")
      (node (ref "J4") (pin "12") (pinfunction "YHI_12") (pintype "bidirectional"))
      (node (ref "R23") (pin "P$1") (pinfunction "1_P$1") (pintype "passive"))
    )
    (net (code "171") (name "R52") (class "Default")
      (node (ref "J4") (pin "9") (pinfunction "GHI_9") (pintype "bidirectional"))
      (node (ref "R24") (pin "P$1") (pinfunction "1_P$1") (pintype "passive"))
    )
    (net (code "172") (name "RELAY_0") (class "Default")
      (node (ref "U4") (pin "59") (pinfunction "P9_1_59") (pintype "bidirectional"))
    )
    (net (code "173") (name "RELAY_1") (class "Default")
      (node (ref "U4") (pin "58") (pinfunction "P9_0_58") (pintype "bidirectional"))
    )
    (net (code "174") (name "RELAY_2") (class "Default")
      (node (ref "U4") (pin "57") (pinfunction "P3_15_57") (pintype "bidirectional"))
    )
    (net (code "175") (name "RELAY_3") (class "Default")
      (node (ref "U4") (pin "56") (pinfunction "P3_14_56") (pintype "bidirectional"))
    )
    (net (code "176") (name "RELAY_6") (class "Default")
      (node (ref "U4") (pin "51") (pinfunction "P2_5_51") (pintype "bidirectional"))
    )
    (net (code "177") (name "RELAY_7") (class "Default")
      (node (ref "U4") (pin "50") (pinfunction "P2_6_50") (pintype "bidirectional"))
    )
    (net (code "178") (name "RESET") (class "Default")
      (node (ref "C57") (pin "P$1") (pinfunction "1_P$1") (pintype "passive"))
      (node (ref "J11") (pin "9") (pinfunction "9_9") (pintype "passive"))
      (node (ref "R18") (pin "P$1") (pinfunction "1_P$1") (pintype "passive"))
      (node (ref "U4") (pin "67") (pinfunction "RES#_67") (pintype "bidirectional"))
    )
    (net (code "179") (name "REXT") (class "Default")
      (node (ref "C47") (pin "P$1") (pinfunction "1_P$1") (pintype "passive"))
      (node (ref "R25") (pin "P$2") (pinfunction "2_P$2") (pintype "passive"))
      (node (ref "U3") (pin "9") (pinfunction "REXT_9") (pintype "input"))
    )
    (net (code "180") (name "RST") (class "Default")
      (node (ref "C91") (pin "P$1") (pinfunction "1_P$1") (pintype "passive"))
      (node (ref "R127") (pin "P$1") (pinfunction "1_P$1") (pintype "passive"))
      (node (ref "U6") (pin "41") (pinfunction "~{RESET}_41") (pintype "input"))
    )
    (net (code "181") (name "RXD0") (class "Default")
      (node (ref "R31") (pin "P$2") (pinfunction "2_P$2") (pintype "passive"))
      (node (ref "U3") (pin "13") (pinfunction "RXD0_13") (pintype "bidirectional"))
    )
    (net (code "182") (name "RXD1") (class "Default")
      (node (ref "R30") (pin "P$2") (pinfunction "2_P$2") (pintype "passive"))
      (node (ref "U3") (pin "12") (pinfunction "RXD1_12") (pintype "bidirectional"))
    )
    (net (code "183") (name "RXER") (class "Default")
      (node (ref "R32") (pin "P$2") (pinfunction "2_P$2") (pintype "passive"))
      (node (ref "U3") (pin "17") (pinfunction "RXER_17") (pintype "bidirectional"))
    )
    (net (code "184") (name "RXM") (class "Default")
      (node (ref "J4") (pin "6") (pinfunction "RD-_6") (pintype "bidirectional"))
      (node (ref "U3") (pin "3") (pinfunction "RXM_3") (pintype "bidirectional"))
    )
    (net (code "185") (name "RXP") (class "Default")
      (node (ref "J4") (pin "3") (pinfunction "RD+_3") (pintype "bidirectional"))
      (node (ref "U3") (pin "4") (pinfunction "RXP_4") (pintype "bidirectional"))
    )
    (net (code "186") (name "SD1_CD") (class "Default")
      (node (ref "U4") (pin "146") (pinfunction "P5_6/AN019_146") (pintype "bidirectional"))
    )
    (net (code "187") (name "SD1_CLK") (class "Default")
      (node (ref "U4") (pin "140") (pinfunction "P5_0/AN016_140") (pintype "bidirectional"))
    )
    (net (code "188") (name "SD1_CMD") (class "Default")
      (node (ref "U4") (pin "141") (pinfunction "P5_1/AN116_141") (pintype "bidirectional"))
    )
    (net (code "189") (name "SD1_DAT0") (class "Default")
      (node (ref "U4") (pin "142") (pinfunction "P5_2/AN017_142") (pintype "bidirectional"))
    )
    (net (code "190") (name "SD1_DAT1") (class "Default")
      (node (ref "U4") (pin "143") (pinfunction "P5_3/AN117_143") (pintype "bidirectional"))
    )
    (net (code "191") (name "SD1_DAT2") (class "Default")
      (node (ref "U4") (pin "144") (pinfunction "P5_4/AN018_144") (pintype "bidirectional"))
    )
    (net (code "192") (name "SD1_DAT3") (class "Default")
      (node (ref "U4") (pin "145") (pinfunction "P5_5/AN118_145") (pintype "bidirectional"))
    )
    (net (code "193") (name "SD1_WP") (class "Default")
      (node (ref "U4") (pin "147") (pinfunction "P5_7/AN119_147") (pintype "bidirectional"))
    )
    (net (code "194") (name "SPI_0_CS_0") (class "Default")
      (node (ref "U4") (pin "129") (pinfunction "P1_3_129") (pintype "bidirectional"))
      (node (ref "U6") (pin "37") (pinfunction "~{CS}_37") (pintype "bidirectional"))
    )
    (net (code "195") (name "SPI_0_MISO") (class "Default")
      (node (ref "U4") (pin "132") (pinfunction "P1_0_132") (pintype "bidirectional"))
      (node (ref "U6") (pin "39") (pinfunction "SDO_39") (pintype "bidirectional"))
    )
    (net (code "196") (name "SPI_0_MOSI") (class "Default")
      (node (ref "U4") (pin "131") (pinfunction "P1_1_131") (pintype "bidirectional"))
      (node (ref "U6") (pin "40") (pinfunction "SDI_40") (pintype "bidirectional"))
    )
    (net (code "197") (name "SPI_0_SCLK") (class "Default")
      (node (ref "U4") (pin "130") (pinfunction "P1_2_130") (pintype "bidirectional"))
      (node (ref "U6") (pin "38") (pinfunction "SCLK_38") (pintype "bidirectional"))
    )
    (net (code "198") (name "SPI_1_CS_0") (class "Default")
      (node (ref "U$1") (pin "P$7") (pinfunction "P$7_P$7") (pintype "bidirectional"))
      (node (ref "U4") (pin "55") (pinfunction "P3_13_55") (pintype "bidirectional"))
    )
    (net (code "199") (name "SPI_1_MISO") (class "Default")
      (node (ref "U$1") (pin "P$5") (pinfunction "P$5_P$5") (pintype "bidirectional"))
      (node (ref "U4") (pin "54") (pinfunction "P2_2_54") (pintype "bidirectional"))
    )
    (net (code "200") (name "SPI_1_MOSI") (class "Default")
      (node (ref "U$1") (pin "P$6") (pinfunction "P$6_P$6") (pintype "bidirectional"))
      (node (ref "U4") (pin "53") (pinfunction "P2_3_53") (pintype "bidirectional"))
    )
    (net (code "201") (name "SPI_1_SCLK") (class "Default")
      (node (ref "U$1") (pin "P$4") (pinfunction "P$4_P$4") (pintype "bidirectional"))
      (node (ref "U4") (pin "52") (pinfunction "P2_4_52") (pintype "bidirectional"))
    )
    (net (code "202") (name "TCK") (class "Default")
      (node (ref "J11") (pin "7") (pinfunction "7_7") (pintype "passive"))
      (node (ref "U4") (pin "88") (pinfunction "P3_0_88") (pintype "bidirectional"))
    )
    (net (code "203") (name "TDI") (class "Default")
      (node (ref "J11") (pin "1") (pinfunction "1_1") (pintype "passive"))
      (node (ref "U4") (pin "91") (pinfunction "P1_10_91") (pintype "bidirectional"))
    )
    (net (code "204") (name "TDO") (class "Default")
      (node (ref "J11") (pin "3") (pinfunction "3_3") (pintype "passive"))
      (node (ref "U4") (pin "90") (pinfunction "P1_9_90") (pintype "bidirectional"))
    )
    (net (code "205") (name "TMS") (class "Default")
      (node (ref "J11") (pin "5") (pinfunction "5_5") (pintype "passive"))
      (node (ref "U4") (pin "89") (pinfunction "P1_8_89") (pintype "bidirectional"))
    )
    (net (code "206") (name "TXM") (class "Default")
      (node (ref "J4") (pin "2") (pinfunction "TD-_2") (pintype "bidirectional"))
      (node (ref "U3") (pin "5") (pinfunction "TXM_5") (pintype "bidirectional"))
    )
    (net (code "207") (name "TXP") (class "Default")
      (node (ref "J4") (pin "1") (pinfunction "TD+_1") (pintype "bidirectional"))
      (node (ref "U3") (pin "6") (pinfunction "TXP_6") (pintype "bidirectional"))
    )
    (net (code "208") (name "UA") (class "Default")
      (node (ref "J9") (pin "P$1") (pinfunction "P$1_P$1") (pintype "bidirectional"))
      (node (ref "R100") (pin "P$2") (pinfunction "2_P$2") (pintype "passive"))
    )
    (net (code "209") (name "UB") (class "Default")
      (node (ref "J9") (pin "P$2") (pinfunction "P$2_P$2") (pintype "bidirectional"))
      (node (ref "R109") (pin "P$2") (pinfunction "2_P$2") (pintype "passive"))
    )
    (net (code "210") (name "UC") (class "Default")
      (node (ref "C93") (pin "P$1") (pinfunction "P$1_P$1") (pintype "bidirectional"))
      (node (ref "J10") (pin "P$1") (pinfunction "P$1_P$1") (pintype "bidirectional"))
      (node (ref "R118") (pin "P$2") (pinfunction "2_P$2") (pintype "passive"))
      (node (ref "U$7") (pin "P$1") (pinfunction "P$1_P$1") (pintype "bidirectional"))
      (node (ref "U7") (pin "P$5") (pinfunction "AC_L_P$5") (pintype "bidirectional"))
    )
    (net (code "211") (name "USBHS_FAULT") (class "Default")
      (node (ref "R12") (pin "P$1") (pinfunction "1_P$1") (pintype "passive"))
      (node (ref "U2") (pin "3") (pinfunction "FLG_3") (pintype "input"))
      (node (ref "U4") (pin "78") (pinfunction "P3_8_78") (pintype "bidirectional"))
    )
    (net (code "212") (name "USBHS_N") (class "Default")
      (node (ref "J3") (pin "D-") (pinfunction "D-_D-") (pintype "bidirectional"))
      (node (ref "U4") (pin "31") (pinfunction "USBHS_DM_31") (pintype "bidirectional"))
    )
    (net (code "213") (name "USBHS_P") (class "Default")
      (node (ref "J3") (pin "D+") (pinfunction "D+_D+") (pintype "bidirectional"))
      (node (ref "U4") (pin "32") (pinfunction "USBHS_DP_32") (pintype "bidirectional"))
    )
    (net (code "214") (name "USBHS_VBUS") (class "Default")
      (node (ref "C11") (pin "P$1") (pinfunction "1_P$1") (pintype "passive"))
      (node (ref "C15") (pin "1") (pinfunction "1_1") (pintype "passive"))
      (node (ref "J3") (pin "VBUS") (pinfunction "VBUS_VBUS") (pintype "power_in"))
      (node (ref "U2") (pin "5") (pinfunction "OUT_5") (pintype "input"))
      (node (ref "U4") (pin "17") (pinfunction "PB_1_17") (pintype "bidirectional"))
    )
    (net (code "215") (name "USBHS_VBUSEN") (class "Default")
      (node (ref "R1") (pin "P$1") (pinfunction "1_P$1") (pintype "passive"))
      (node (ref "U2") (pin "1") (pinfunction "EN_1") (pintype "input"))
    )
    (net (code "216") (name "USB_N") (class "Default")
      (node (ref "R5") (pin "P$1") (pinfunction "1_P$1") (pintype "passive"))
      (node (ref "U4") (pin "46") (pinfunction "USB_DM_46") (pintype "bidirectional"))
    )
    (net (code "217") (name "USB_P") (class "Default")
      (node (ref "R6") (pin "P$1") (pinfunction "1_P$1") (pintype "passive"))
      (node (ref "U4") (pin "47") (pinfunction "USB_DP_47") (pintype "bidirectional"))
    )
    (net (code "218") (name "USB_VBUS_B") (class "Default")
      (node (ref "R4") (pin "P$1") (pinfunction "1_P$1") (pintype "passive"))
      (node (ref "U4") (pin "44") (pinfunction "P4_7_44") (pintype "bidirectional"))
    )
    (net (code "219") (name "VAN") (class "Default")
      (node (ref "C80") (pin "P$2") (pinfunction "2_P$2") (pintype "passive"))
      (node (ref "R108") (pin "P$1") (pinfunction "1_P$1") (pintype "passive"))
      (node (ref "U6") (pin "14") (pinfunction "V1N_14") (pintype "input"))
    )
    (net (code "220") (name "VAP") (class "Default")
      (node (ref "C79") (pin "P$2") (pinfunction "2_P$2") (pintype "passive"))
      (node (ref "R106") (pin "P$1") (pinfunction "1_P$1") (pintype "passive"))
      (node (ref "R107") (pin "P$1") (pinfunction "1_P$1") (pintype "passive"))
      (node (ref "U6") (pin "13") (pinfunction "V1P_13") (pintype "input"))
    )
    (net (code "221") (name "VBN") (class "Default")
      (node (ref "C82") (pin "P$2") (pinfunction "2_P$2") (pintype "passive"))
      (node (ref "R117") (pin "P$1") (pinfunction "1_P$1") (pintype "passive"))
      (node (ref "U6") (pin "16") (pinfunction "V2N_16") (pintype "input"))
    )
    (net (code "222") (name "VBP") (class "Default")
      (node (ref "C81") (pin "P$2") (pinfunction "2_P$2") (pintype "passive"))
      (node (ref "R115") (pin "P$1") (pinfunction "1_P$1") (pintype "passive"))
      (node (ref "R116") (pin "P$1") (pinfunction "1_P$1") (pintype "passive"))
      (node (ref "U6") (pin "15") (pinfunction "V2P_15") (pintype "input"))
    )
    (net (code "223") (name "VCC") (class "Default")
      (node (ref "C94") (pin "P$1") (pinfunction "1_P$1") (pintype "passive"))
      (node (ref "C95") (pin "P$1") (pinfunction "1_P$1") (pintype "passive"))
      (node (ref "C96") (pin "1") (pinfunction "1_1") (pintype "passive"))
      (node (ref "C97") (pin "P$1") (pinfunction "1_P$1") (pintype "passive"))
      (node (ref "IC3") (pin "1") (pinfunction "IN_1") (pintype "input"))
      (node (ref "IC4") (pin "1") (pinfunction "IN_1") (pintype "input"))
      (node (ref "U$8") (pin "P+") (pinfunction "+_P+") (pintype "passive"))
      (node (ref "U7") (pin "P$2") (pinfunction "VOUT+_P$2") (pintype "bidirectional"))
    )
    (net (code "224") (name "VCL_F(FLASH)") (class "Default")
      (node (ref "C36") (pin "P$2") (pinfunction "2_P$2") (pintype "passive"))
      (node (ref "U4") (pin "112") (pinfunction "VCL_F(FLASH)_112") (pintype "bidirectional"))
    )
    (net (code "225") (name "VCN") (class "Default")
      (node (ref "C84") (pin "P$2") (pinfunction "2_P$2") (pintype "passive"))
      (node (ref "R126") (pin "P$1") (pinfunction "1_P$1") (pintype "passive"))
      (node (ref "U6") (pin "18") (pinfunction "V3N_18") (pintype "input"))
    )
    (net (code "226") (name "VCP") (class "Default")
      (node (ref "C83") (pin "P$2") (pinfunction "2_P$2") (pintype "passive"))
      (node (ref "R124") (pin "P$1") (pinfunction "1_P$1") (pintype "passive"))
      (node (ref "R125") (pin "P$1") (pinfunction "1_P$1") (pintype "passive"))
      (node (ref "U6") (pin "17") (pinfunction "V3P_17") (pintype "input"))
    )
    (net (code "227") (name "VDD") (class "Default")
      (node (ref "C1") (pin "P$2") (pinfunction "2_P$2") (pintype "passive"))
      (node (ref "C10") (pin "P$2") (pinfunction "2_P$2") (pintype "passive"))
      (node (ref "C13") (pin "P$2") (pinfunction "2_P$2") (pintype "passive"))
      (node (ref "C14") (pin "P$2") (pinfunction "2_P$2") (pintype "passive"))
      (node (ref "C2") (pin "P$2") (pinfunction "2_P$2") (pintype "passive"))
      (node (ref "C30") (pin "P$2") (pinfunction "2_P$2") (pintype "passive"))
      (node (ref "C32") (pin "P$1") (pinfunction "1_P$1") (pintype "passive"))
      (node (ref "C48") (pin "1") (pinfunction "1_1") (pintype "passive"))
      (node (ref "C49") (pin "P$1") (pinfunction "1_P$1") (pintype "passive"))
      (node (ref "C54") (pin "P$2") (pinfunction "2_P$2") (pintype "passive"))
      (node (ref "C55") (pin "P$2") (pinfunction "2_P$2") (pintype "passive"))
      (node (ref "C56") (pin "P$2") (pinfunction "2_P$2") (pintype "passive"))
      (node (ref "C58") (pin "P$1") (pinfunction "1_P$1") (pintype "passive"))
      (node (ref "C59") (pin "P$1") (pinfunction "1_P$1") (pintype "passive"))
      (node (ref "C60") (pin "P$1") (pinfunction "1_P$1") (pintype "passive"))
      (node (ref "C61") (pin "P$2") (pinfunction "2_P$2") (pintype "passive"))
      (node (ref "C87") (pin "P$2") (pinfunction "2_P$2") (pintype "passive"))
      (node (ref "C88") (pin "P$2") (pinfunction "2_P$2") (pintype "passive"))
      (node (ref "C92") (pin "P$1") (pinfunction "1_P$1") (pintype "passive"))
      (node (ref "C98") (pin "P$1") (pinfunction "1_P$1") (pintype "passive"))
      (node (ref "C99") (pin "1") (pinfunction "1_1") (pintype "passive"))
      (node (ref "FB2/2") (pin "1") (pinfunction "P$1_1") (pintype "bidirectional"))
      (node (ref "IC4") (pin "3") (pinfunction "OUT_3") (pintype "output"))
      (node (ref "J11") (pin "2") (pinfunction "2_2") (pintype "passive"))
      (node (ref "J11") (pin "4") (pinfunction "4_4") (pintype "passive"))
      (node (ref "R127") (pin "P$2") (pinfunction "2_P$2") (pintype "passive"))
      (node (ref "R128") (pin "P$1") (pinfunction "1_P$1") (pintype "passive"))
      (node (ref "R18") (pin "P$2") (pinfunction "2_P$2") (pintype "passive"))
      (node (ref "R23") (pin "P$2") (pinfunction "2_P$2") (pintype "passive"))
      (node (ref "R24") (pin "P$2") (pinfunction "2_P$2") (pintype "passive"))
      (node (ref "R26") (pin "P$2") (pinfunction "2_P$2") (pintype "passive"))
      (node (ref "R27") (pin "P$2") (pinfunction "2_P$2") (pintype "passive"))
      (node (ref "R28") (pin "P$2") (pinfunction "2_P$2") (pintype "passive"))
      (node (ref "R29") (pin "P$2") (pinfunction "2_P$2") (pintype "passive"))
      (node (ref "U$1") (pin "P$1") (pinfunction "P$1_P$1") (pintype "bidirectional"))
      (node (ref "U3") (pin "14") (pinfunction "VDDIO_14") (pintype "power_in"))
      (node (ref "U4") (pin "110") (pinfunction "VCC(IO)5_110") (pintype "bidirectional"))
      (node (ref "U4") (pin "123") (pinfunction "VCC(IO)6_123") (pintype "bidirectional"))
      (node (ref "U4") (pin "138") (pinfunction "VCC(IO)7_138") (pintype "bidirectional"))
      (node (ref "U4") (pin "149") (pinfunction "VCC(IO)8_149") (pintype "bidirectional"))
      (node (ref "U4") (pin "154") (pinfunction "VREFH_154") (pintype "bidirectional"))
      (node (ref "U4") (pin "155") (pinfunction "AVCC0_155") (pintype "bidirectional"))
      (node (ref "U4") (pin "158") (pinfunction "VREFH0_158") (pintype "bidirectional"))
      (node (ref "U4") (pin "171") (pinfunction "VCC(IO)9_171") (pintype "bidirectional"))
      (node (ref "U4") (pin "25") (pinfunction "VCC1_25") (pintype "bidirectional"))
      (node (ref "U4") (pin "26") (pinfunction "AVCC_SUBHS_26") (pintype "bidirectional"))
      (node (ref "U4") (pin "34") (pinfunction "VCC_USBHS_34") (pintype "bidirectional"))
      (node (ref "U4") (pin "48") (pinfunction "VCC_USB_48") (pintype "bidirectional"))
      (node (ref "U4") (pin "61") (pinfunction "VCC(IO)2_61") (pintype "bidirectional"))
      (node (ref "U4") (pin "84") (pinfunction "VCC(IO)3_84") (pintype "bidirectional"))
      (node (ref "U4") (pin "97") (pinfunction "VCC(IO)4_97") (pintype "bidirectional"))
      (node (ref "U6") (pin "1") (pinfunction "AVDD_1") (pintype "power_in"))
      (node (ref "U6") (pin "48") (pinfunction "DVDD_48") (pintype "power_in"))
    )
    (net (code "228") (name "VDD1P8") (class "Default")
      (node (ref "C89") (pin "P$1") (pinfunction "1_P$1") (pintype "passive"))
      (node (ref "C90") (pin "P$1") (pinfunction "1_P$1") (pintype "passive"))
      (node (ref "U6") (pin "42") (pinfunction "VDD18_2_42") (pintype "power_in"))
      (node (ref "U6") (pin "43") (pinfunction "VDD18_43") (pintype "power_in"))
    )
    (net (code "229") (name "VDD5") (class "Default")
      (node (ref "C100") (pin "P$1") (pinfunction "1_P$1") (pintype "passive"))
      (node (ref "C101") (pin "1") (pinfunction "1_1") (pintype "passive"))
      (node (ref "C5") (pin "P$1") (pinfunction "1_P$1") (pintype "passive"))
      (node (ref "C8") (pin "P$1") (pinfunction "1_P$1") (pintype "passive"))
      (node (ref "IC3") (pin "3") (pinfunction "OUT_3") (pintype "output"))
      (node (ref "R1") (pin "P$2") (pinfunction "2_P$2") (pintype "passive"))
      (node (ref "R12") (pin "P$2") (pinfunction "2_P$2") (pintype "passive"))
      (node (ref "R129") (pin "P$1") (pinfunction "1_P$1") (pintype "passive"))
      (node (ref "U2") (pin "4") (pinfunction "VIN_4") (pintype "input"))
    )
    (net (code "230") (name "VDD_1.2") (class "Default")
      (node (ref "C45") (pin "P$1") (pinfunction "1_P$1") (pintype "passive"))
      (node (ref "C46") (pin "P$1") (pinfunction "1_P$1") (pintype "passive"))
      (node (ref "U3") (pin "1") (pinfunction "VDD_1.2_1") (pintype "power_in"))
    )
    (net (code "231") (name "VO") (class "Default")
      (node (ref "U$1") (pin "P$2") (pinfunction "P$2_P$2") (pintype "bidirectional"))
    )
    (net (code "232") (name "VREF") (class "Default")
      (node (ref "C85") (pin "P$1") (pinfunction "1_P$1") (pintype "passive"))
      (node (ref "C86") (pin "P$1") (pinfunction "1_P$1") (pintype "passive"))
      (node (ref "U6") (pin "11") (pinfunction "VREF_11") (pintype "output"))
    )
    (net (code "233") (name "WARNOUT") (class "Default")
      (node (ref "U6") (pin "29") (pinfunction "WARNOUT_29") (pintype "output"))
    )
    (net (code "234") (name "WIFI_GP0") (class "Default")
      (node (ref "U$1") (pin "P$10") (pinfunction "P$10_P$10") (pintype "bidirectional"))
    )
    (net (code "235") (name "WIFI_RST") (class "Default")
      (node (ref "U$1") (pin "P$9") (pinfunction "P$9_P$9") (pintype "bidirectional"))
    )
    (net (code "236") (name "XCIN") (class "Default")
      (node (ref "C50") (pin "P$1") (pinfunction "1_P$1") (pintype "passive"))
      (node (ref "U4") (pin "20") (pinfunction "XCIN_20") (pintype "bidirectional"))
      (node (ref "X3") (pin "P$1") (pinfunction "P$1_P$1") (pintype "bidirectional"))
    )
    (net (code "237") (name "XCOUT") (class "Default")
      (node (ref "C51") (pin "P$1") (pinfunction "1_P$1") (pintype "passive"))
      (node (ref "U4") (pin "21") (pinfunction "XCOUT_21") (pintype "bidirectional"))
      (node (ref "X3") (pin "P$2") (pinfunction "P$2_P$2") (pintype "bidirectional"))
    )
    (net (code "238") (name "XII") (class "Default")
      (node (ref "C42") (pin "P$1") (pinfunction "1_P$1") (pintype "passive"))
      (node (ref "U$3") (pin "1") (pinfunction "1_1") (pintype "bidirectional"))
      (node (ref "U3") (pin "8") (pinfunction "XI_8") (pintype "input"))
    )
    (net (code "239") (name "XOO") (class "Default")
      (node (ref "C41") (pin "P$1") (pinfunction "1_P$1") (pintype "passive"))
      (node (ref "U$3") (pin "3") (pinfunction "3_3") (pintype "bidirectional"))
      (node (ref "U3") (pin "7") (pinfunction "XO_7") (pintype "output"))
    )
    (net (code "240") (name "XTAL1") (class "Default")
      (node (ref "C52") (pin "P$1") (pinfunction "1_P$1") (pintype "passive"))
      (node (ref "U4") (pin "23") (pinfunction "P2_13/XTAL_23") (pintype "bidirectional"))
      (node (ref "X4") (pin "1") (pinfunction "1_1") (pintype "bidirectional"))
    )
    (net (code "241") (name "XTAL2") (class "Default")
      (node (ref "C53") (pin "P$1") (pinfunction "1_P$1") (pintype "passive"))
      (node (ref "U4") (pin "24") (pinfunction "P2_12/EXTAL_24") (pintype "bidirectional"))
      (node (ref "X4") (pin "3") (pinfunction "3_3") (pintype "bidirectional"))
    )
    (net (code "242") (name "ZX0") (class "Default")
      (node (ref "U6") (pin "22") (pinfunction "ZX0_22") (pintype "output"))
    )
    (net (code "243") (name "ZX1") (class "Default")
      (node (ref "U6") (pin "23") (pinfunction "ZX1_23") (pintype "output"))
    )
    (net (code "244") (name "ZX2") (class "Default")
      (node (ref "U6") (pin "24") (pinfunction "ZX2_24") (pintype "output"))
    )
    (net (code "245") (name "unconnected-(U4-VBAT-Pad18)") (class "Default")
      (node (ref "U4") (pin "18") (pinfunction "VBAT_18") (pintype "bidirectional"))
    )
    (net (code "246") (name "unconnected-(U6-NC-Pad46)") (class "Default")
      (node (ref "U6") (pin "46") (pinfunction "NC_46") (pintype "no_connect"))
    )
    (net (code "247") (name "unconnected-(U6-NC_2-Pad35)") (class "Default")
      (node (ref "U6") (pin "35") (pinfunction "NC_2_35") (pintype "no_connect"))
    )
    (net (code "248") (name "unconnected-(U6-NC_3-Pad45)") (class "Default")
      (node (ref "U6") (pin "45") (pinfunction "NC_3_45") (pintype "no_connect"))
    )
    (net (code "249") (name "unconnected-(U7-NC1-PadP$1)") (class "Default")
      (node (ref "U7") (pin "P$1") (pinfunction "NC1_P$1") (pintype "bidirectional"))
    )
    (net (code "250") (name "unconnected-(U7-NC2-PadP$4)") (class "Default")
      (node (ref "U7") (pin "P$4") (pinfunction "NC2_P$4") (pintype "bidirectional"))
    )
    (net (code "251") (name "unconnected-(U7-NC3-PadP$7)") (class "Default")
      (node (ref "U7") (pin "P$7") (pinfunction "NC3_P$7") (pintype "bidirectional"))
    )
  )
)
